# S140039_EMS_3HP_DS.net
KiCad netlist of a schematic drawn in EAGLE
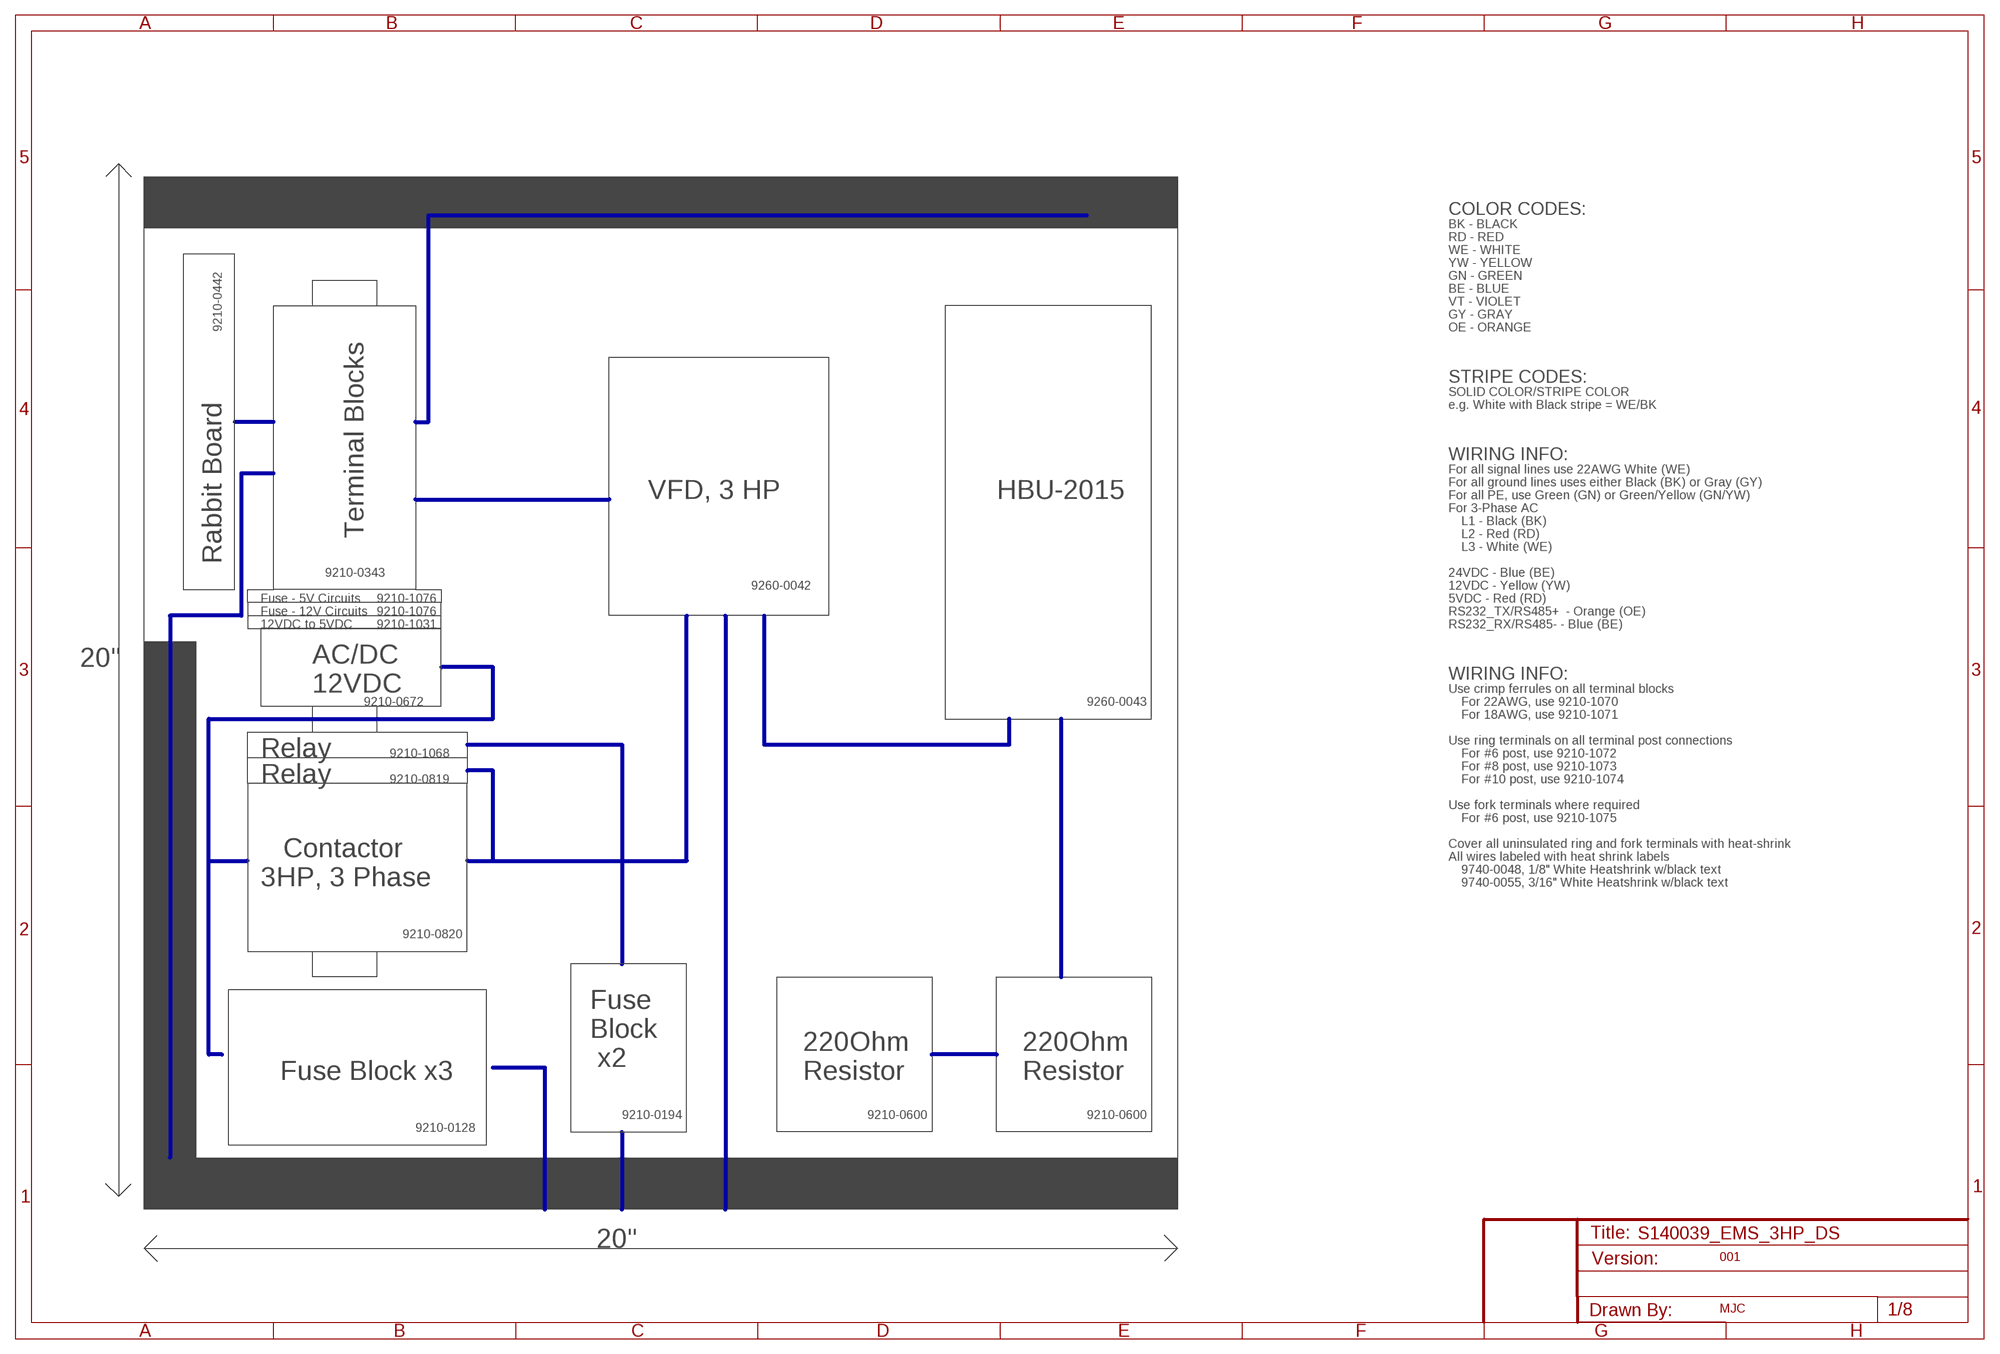
[diagram p0: schematic, sheet 1]
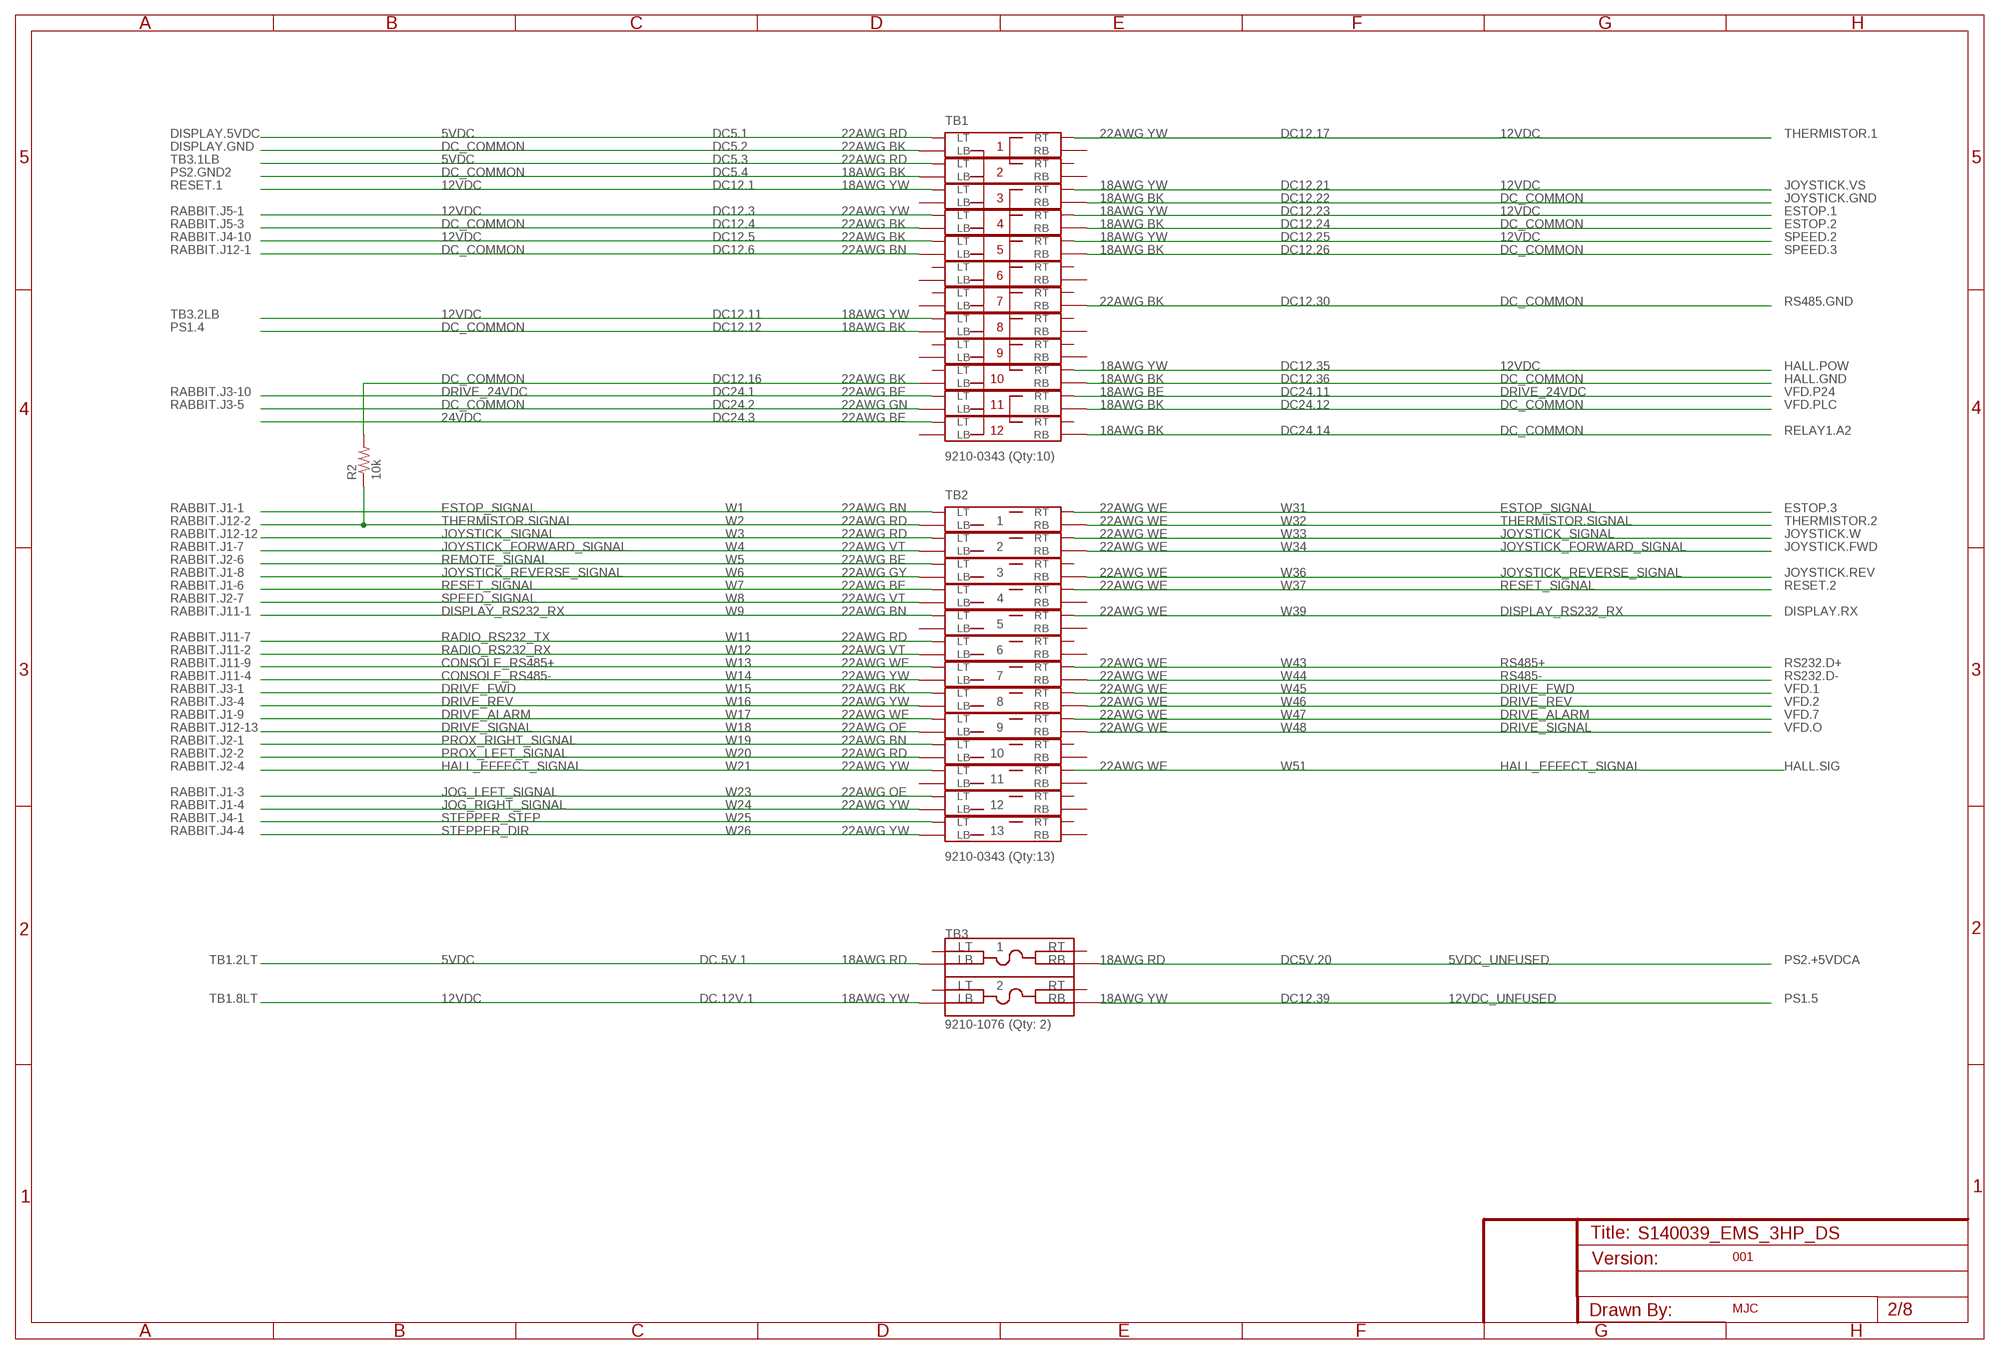
[diagram p1: schematic, sheet 2]
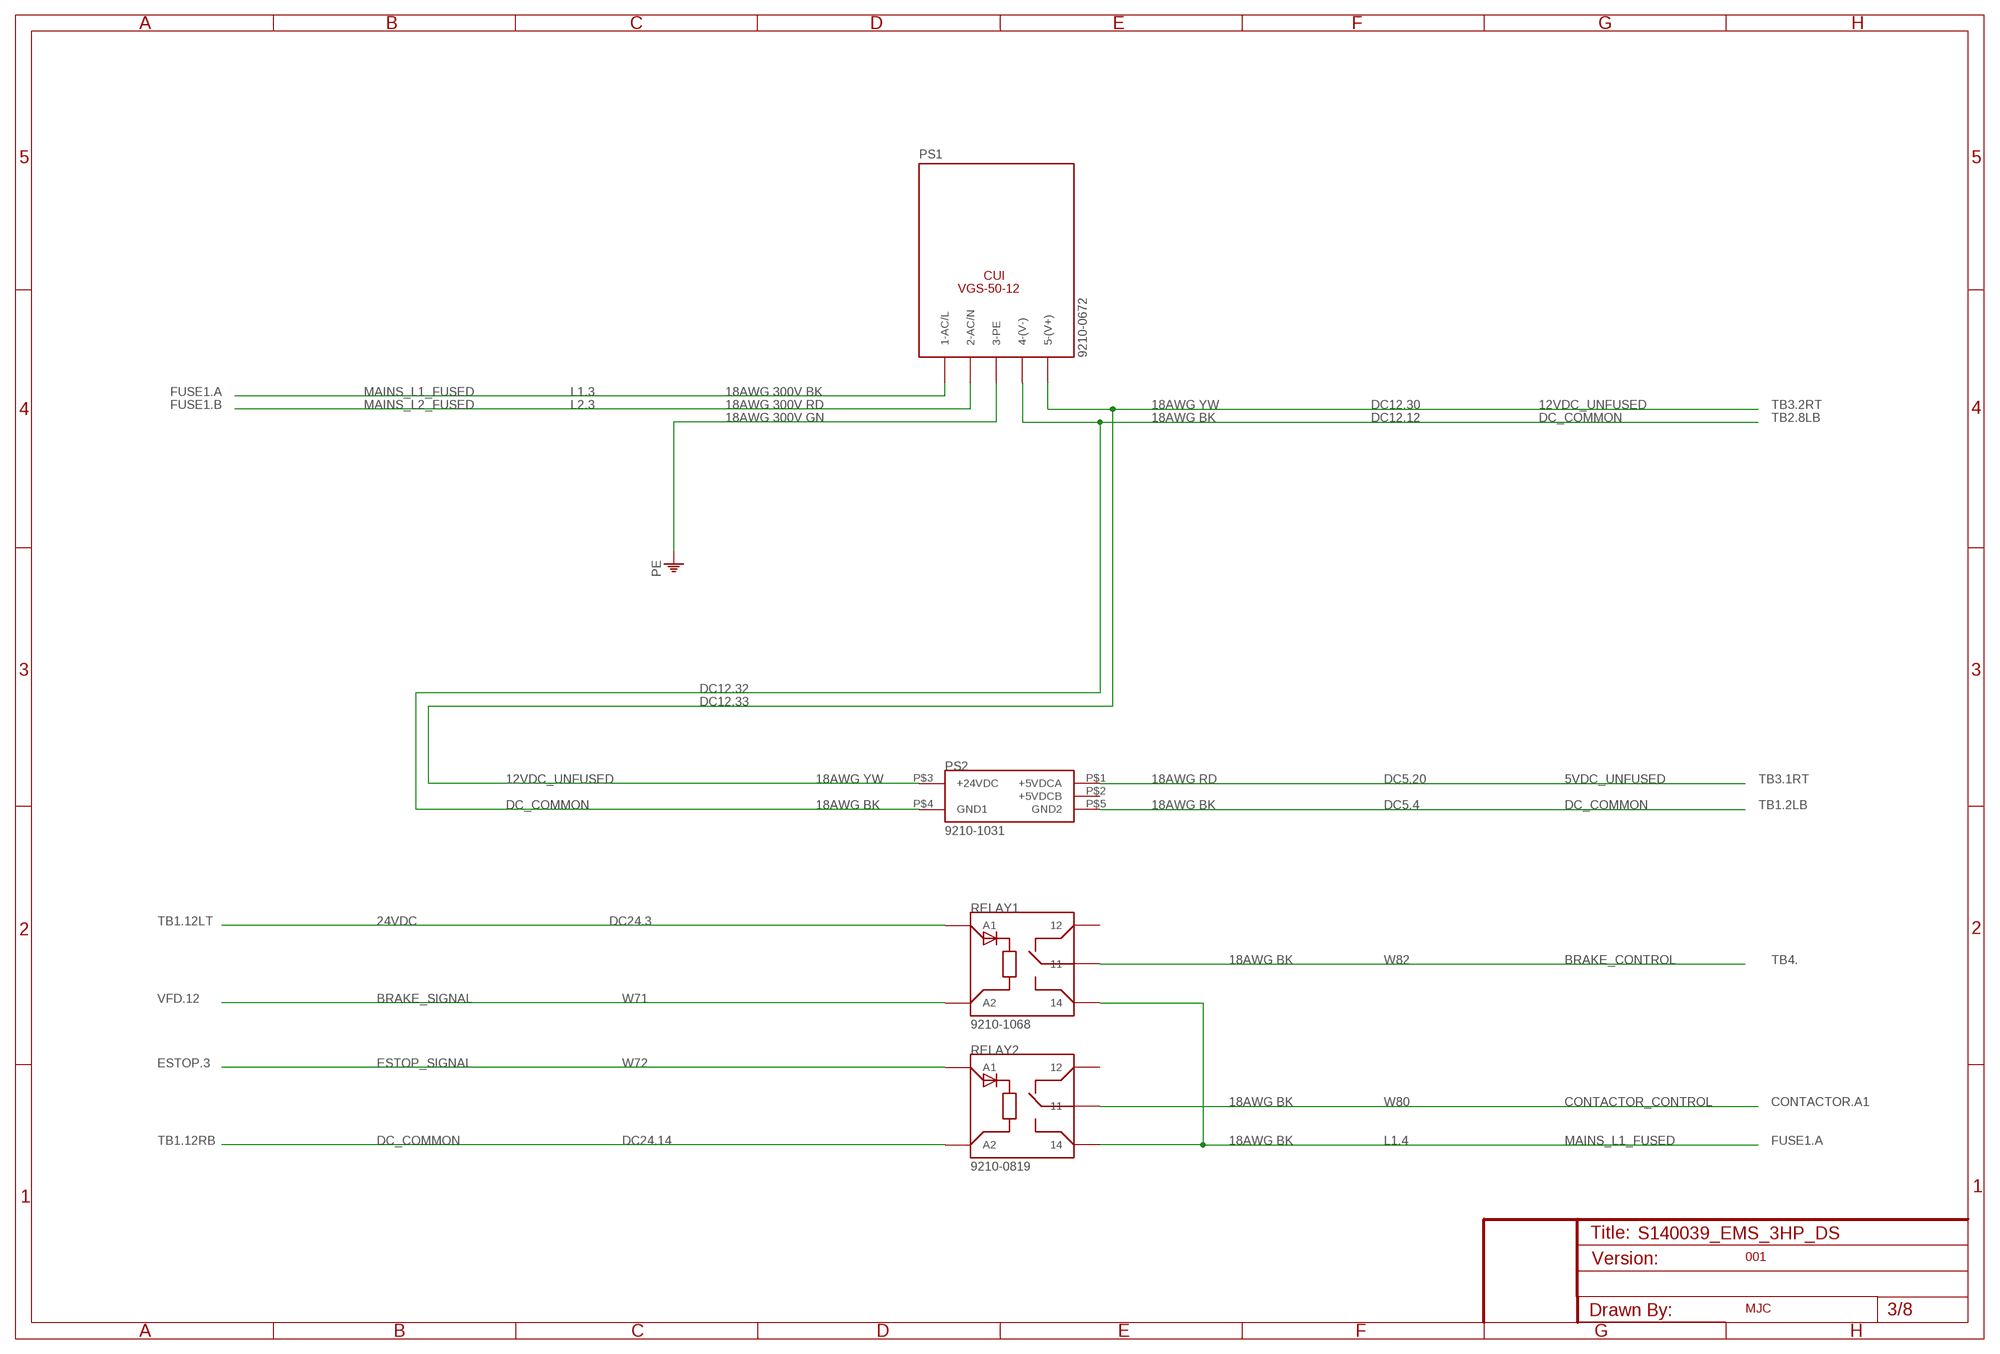
[diagram p2: schematic, sheet 3]
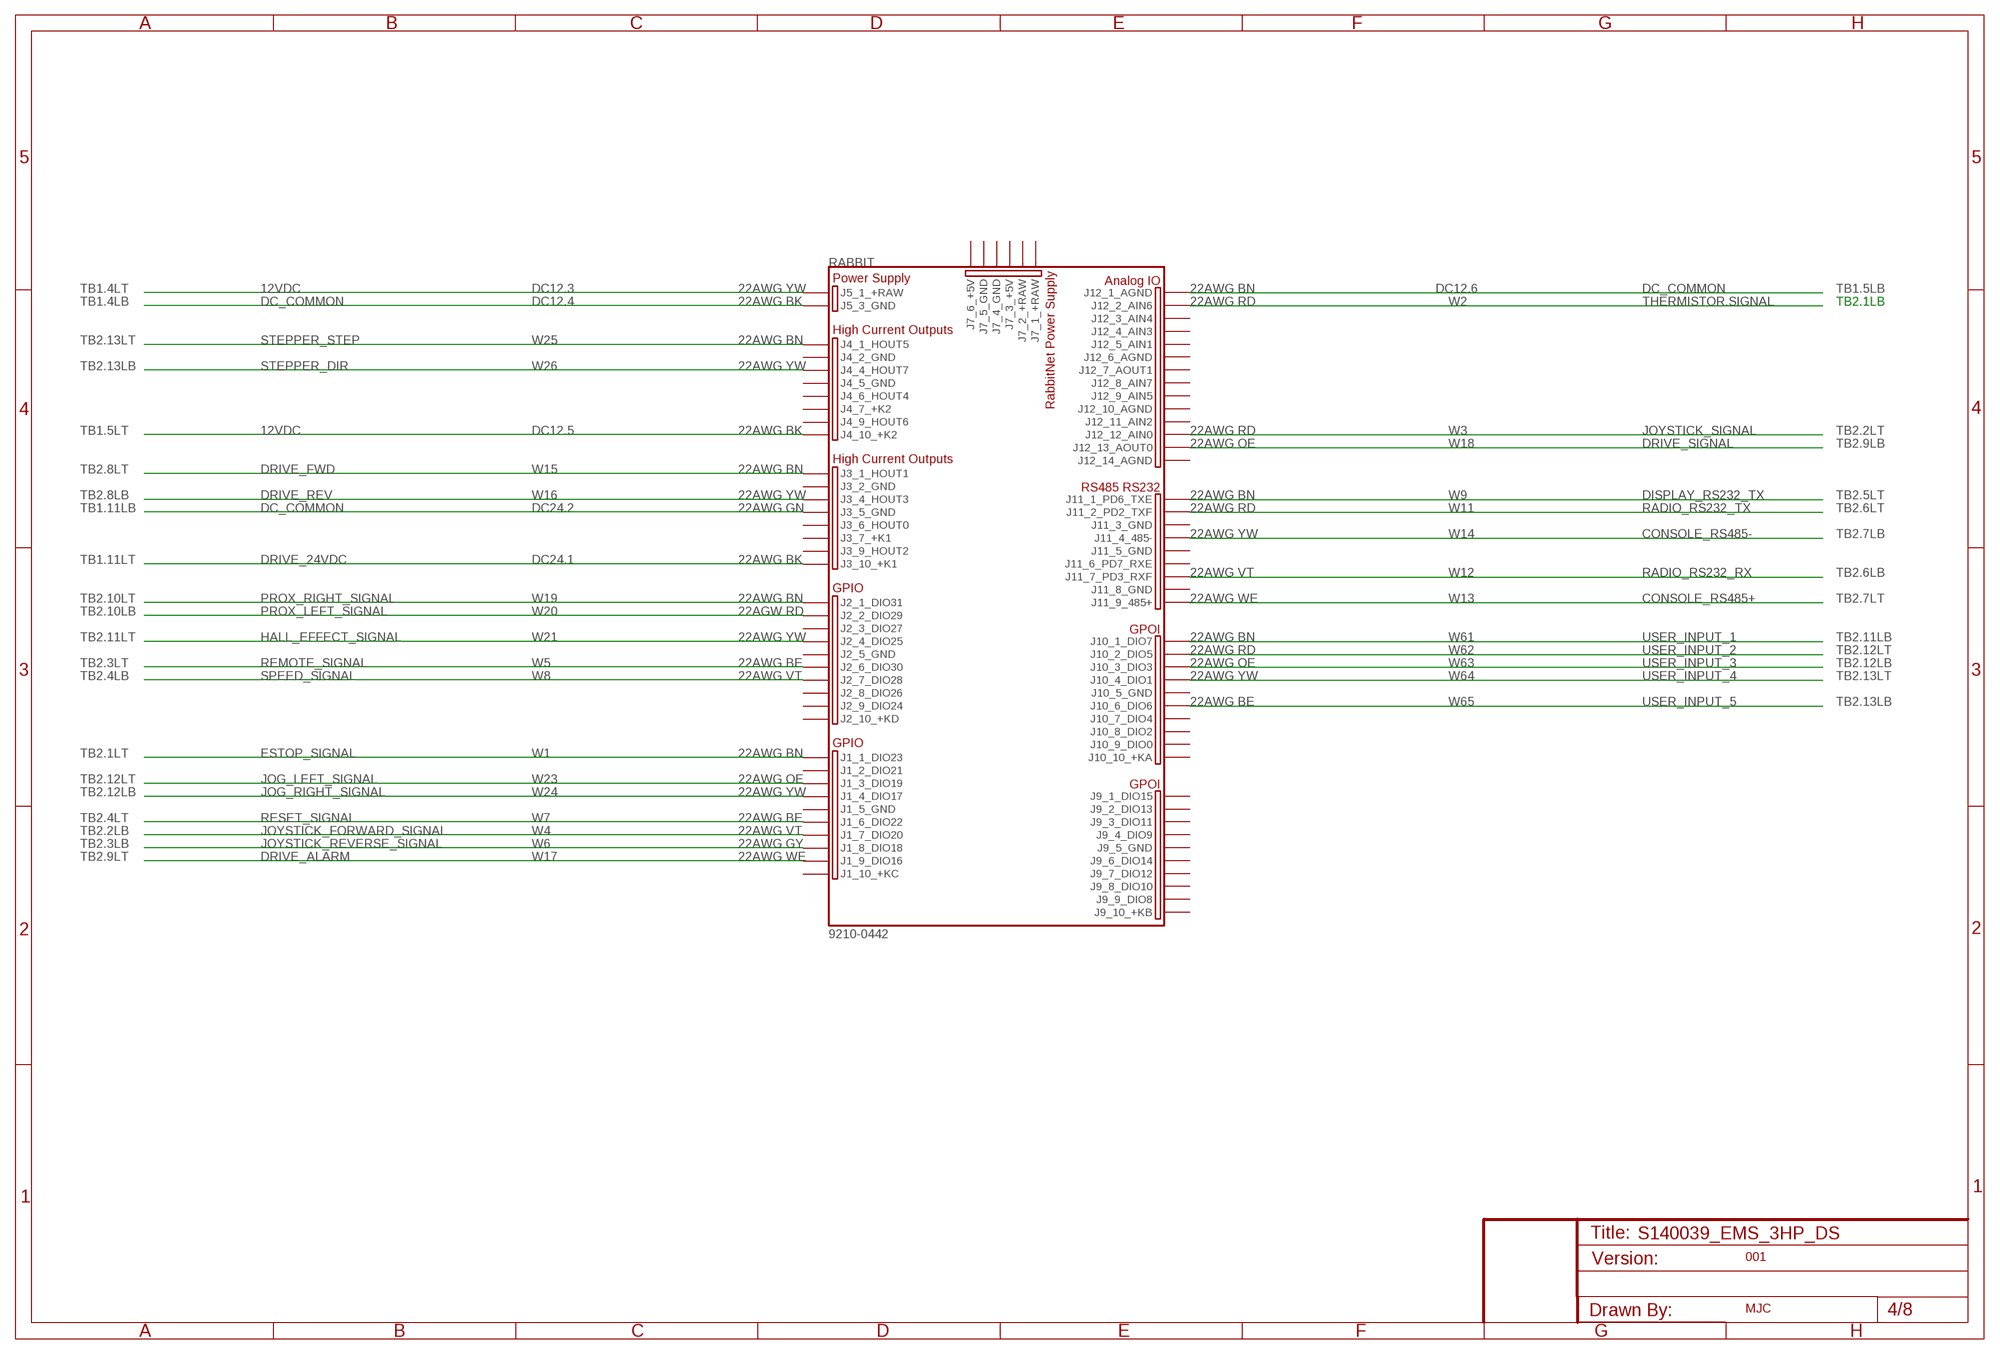
[diagram p3: schematic, sheet 4]
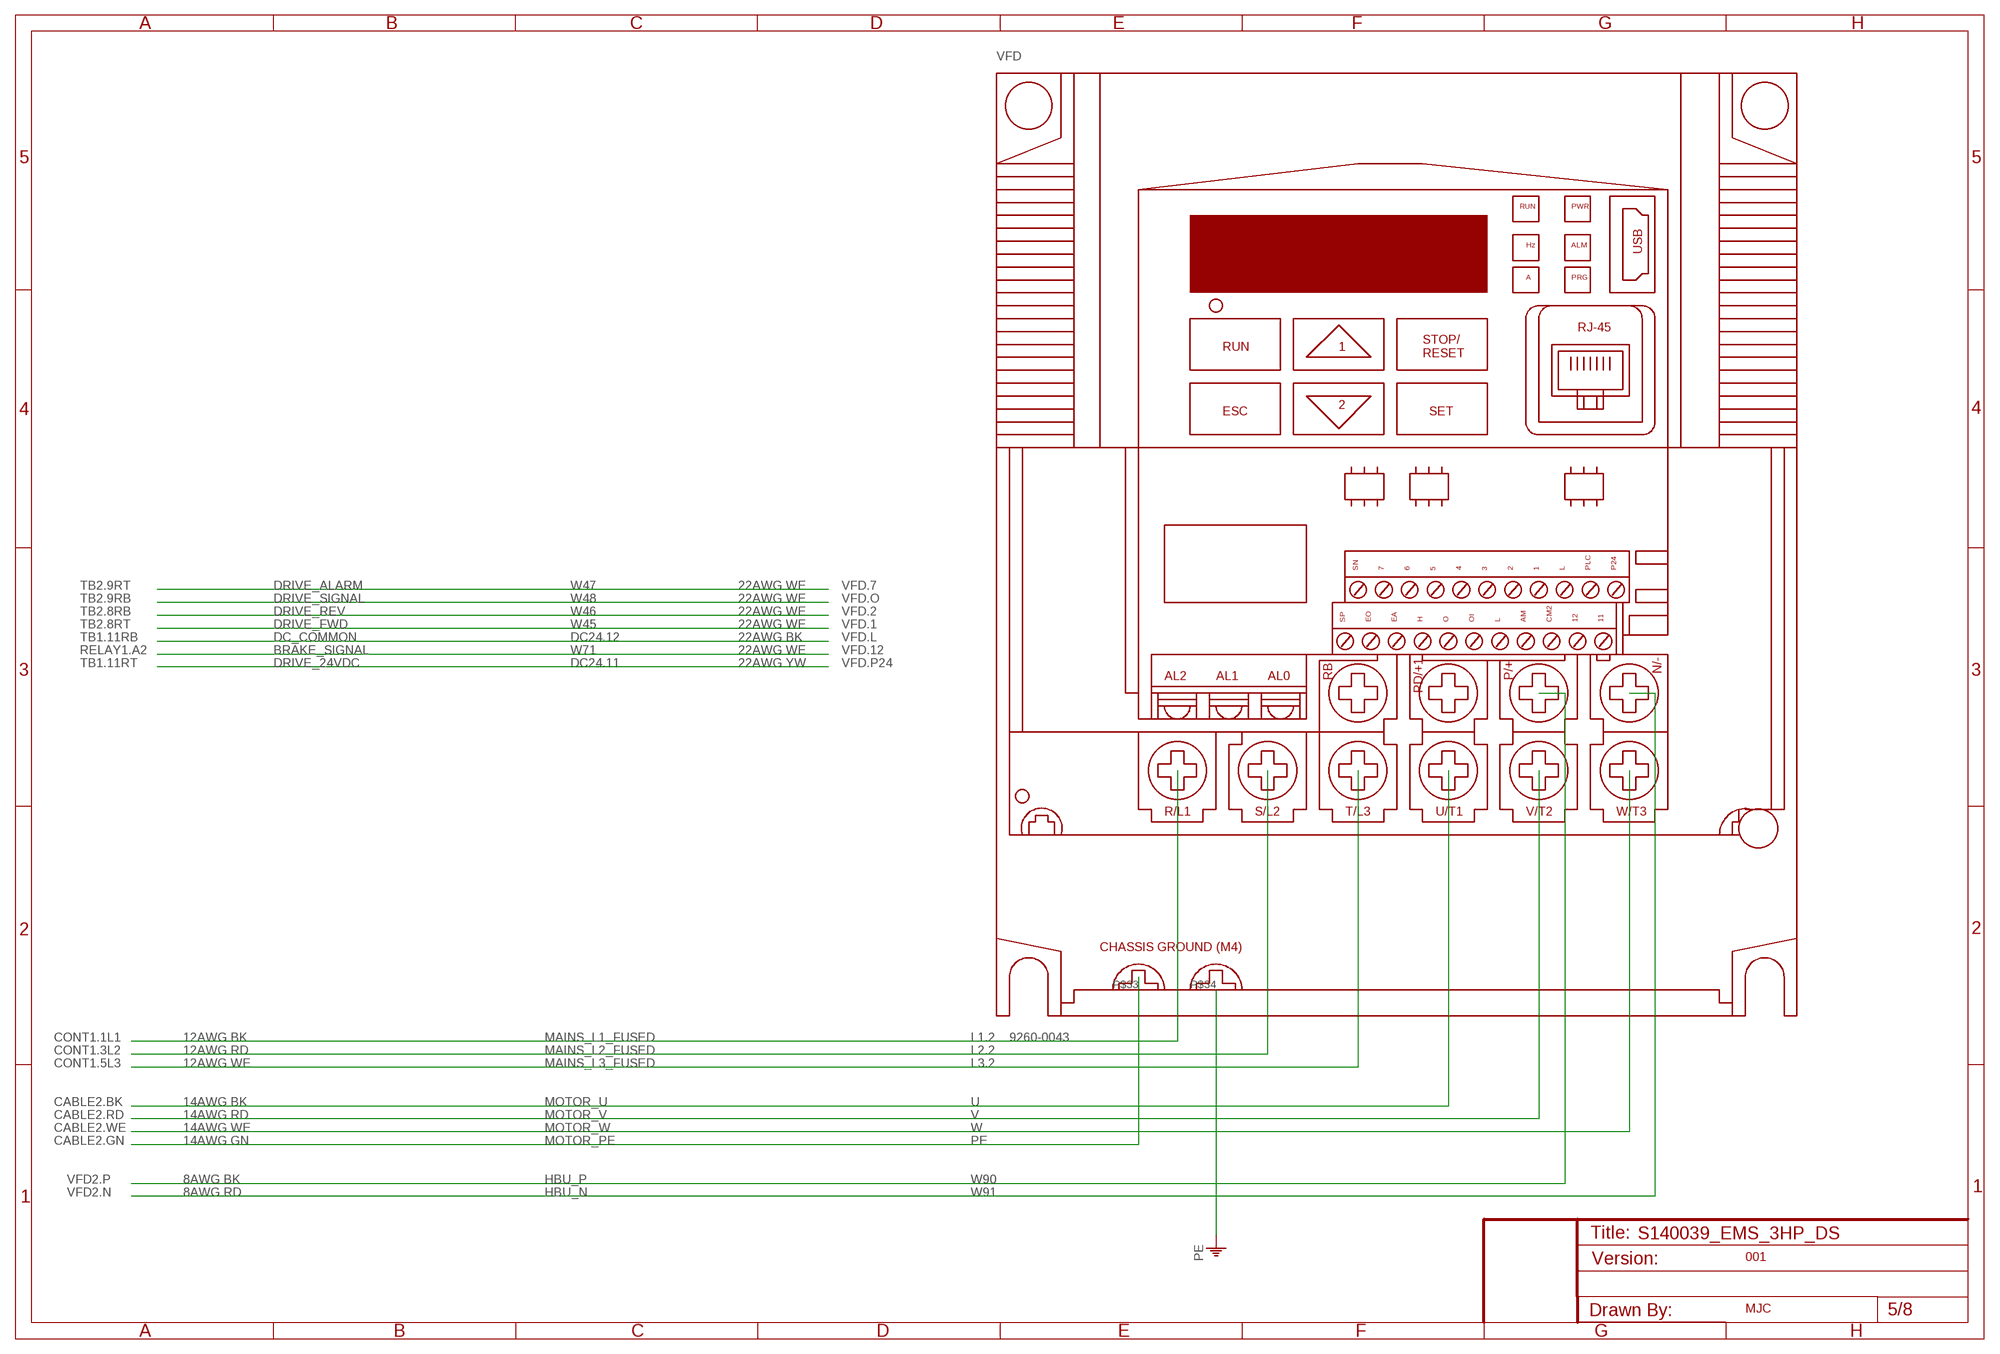
[diagram p4: schematic, sheet 5]
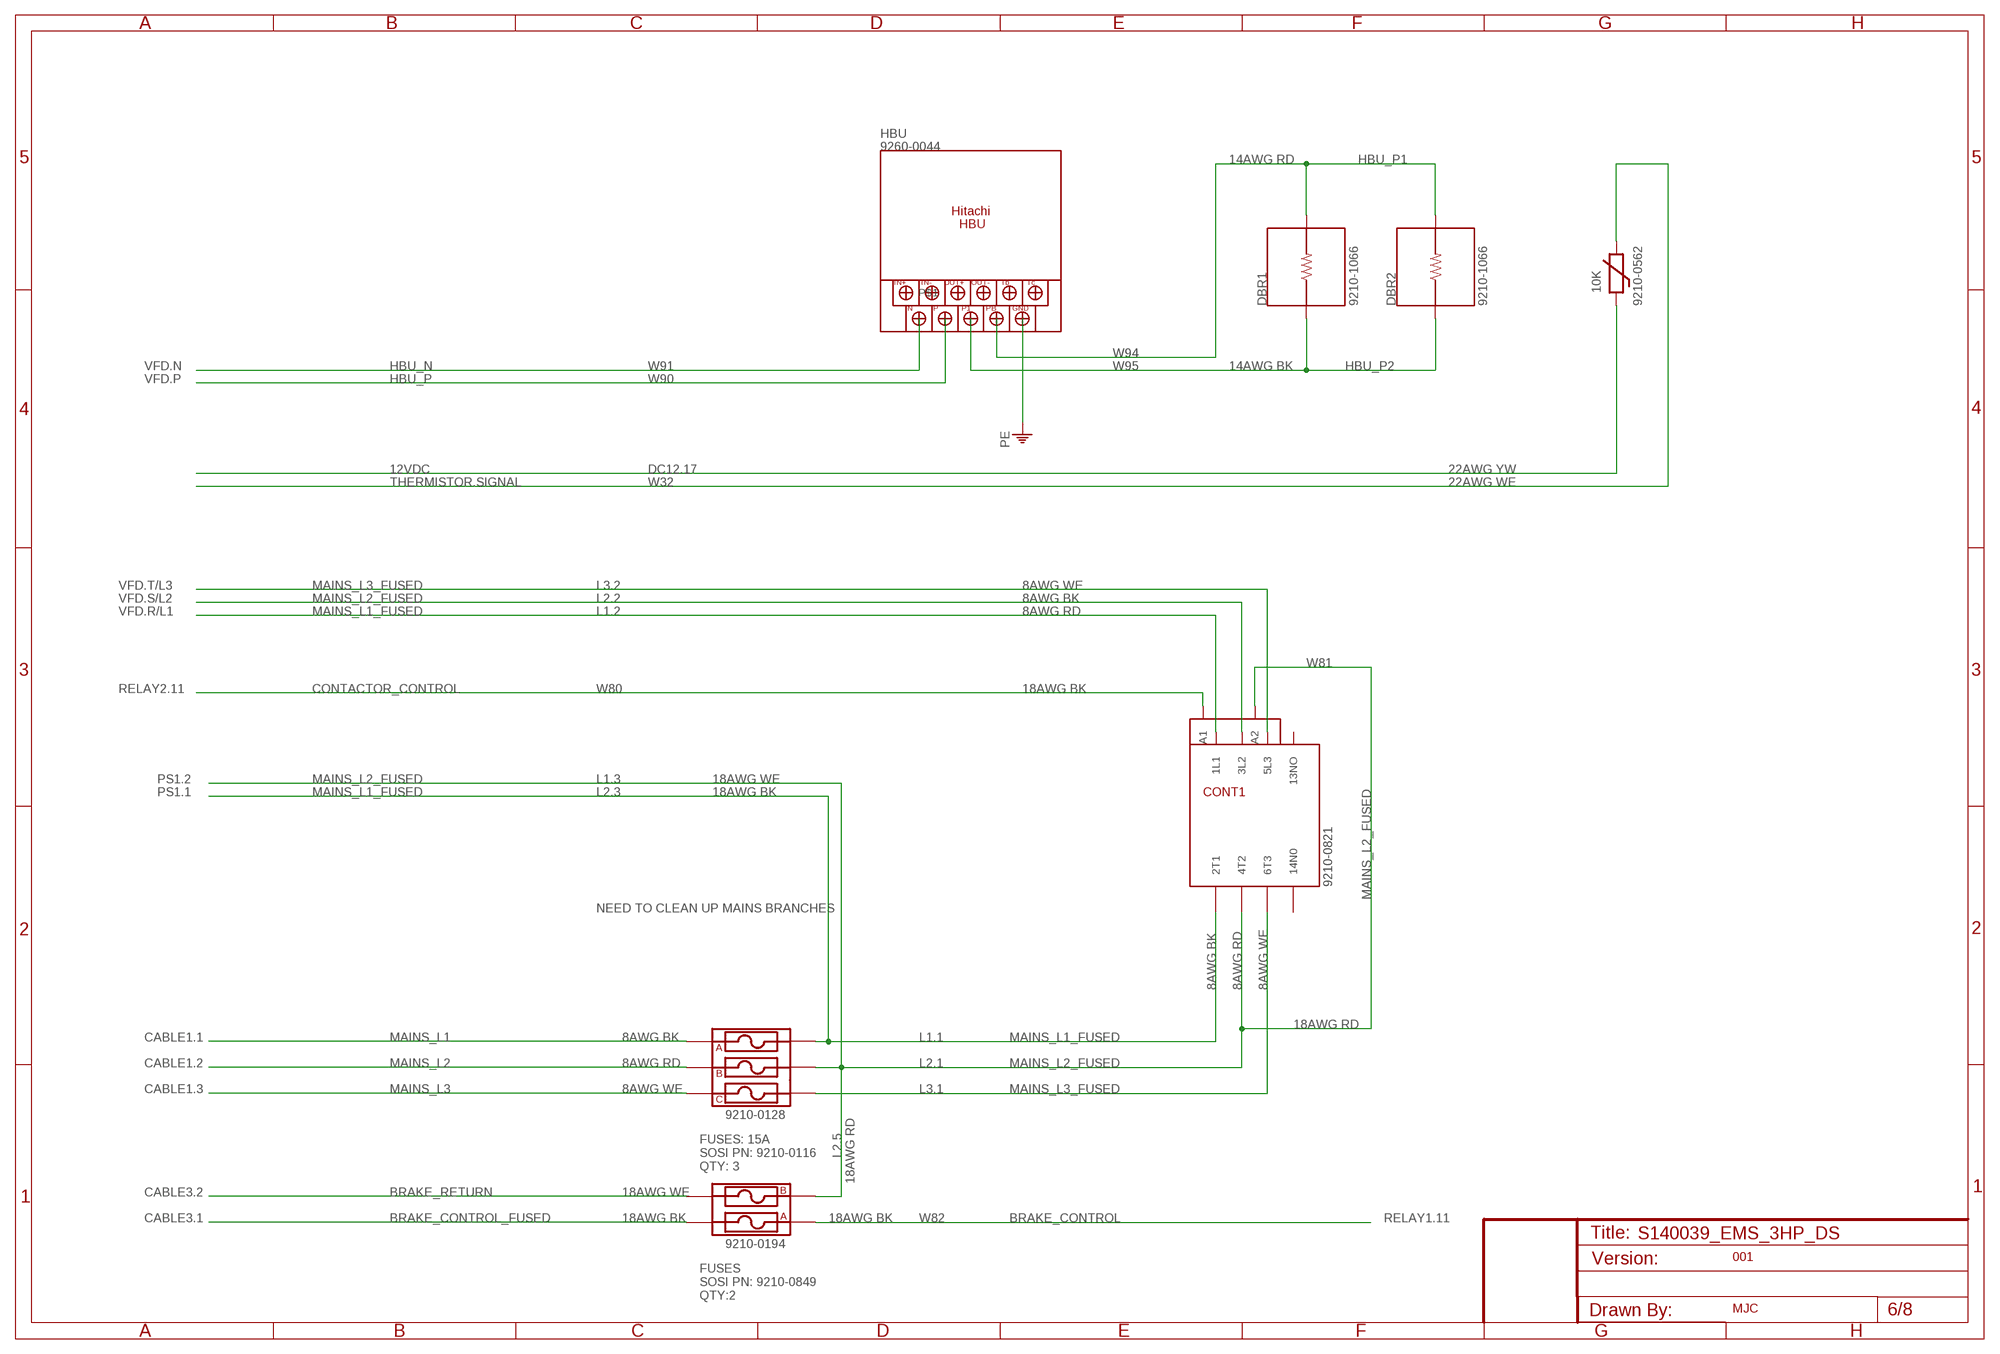
[diagram p5: schematic, sheet 6]
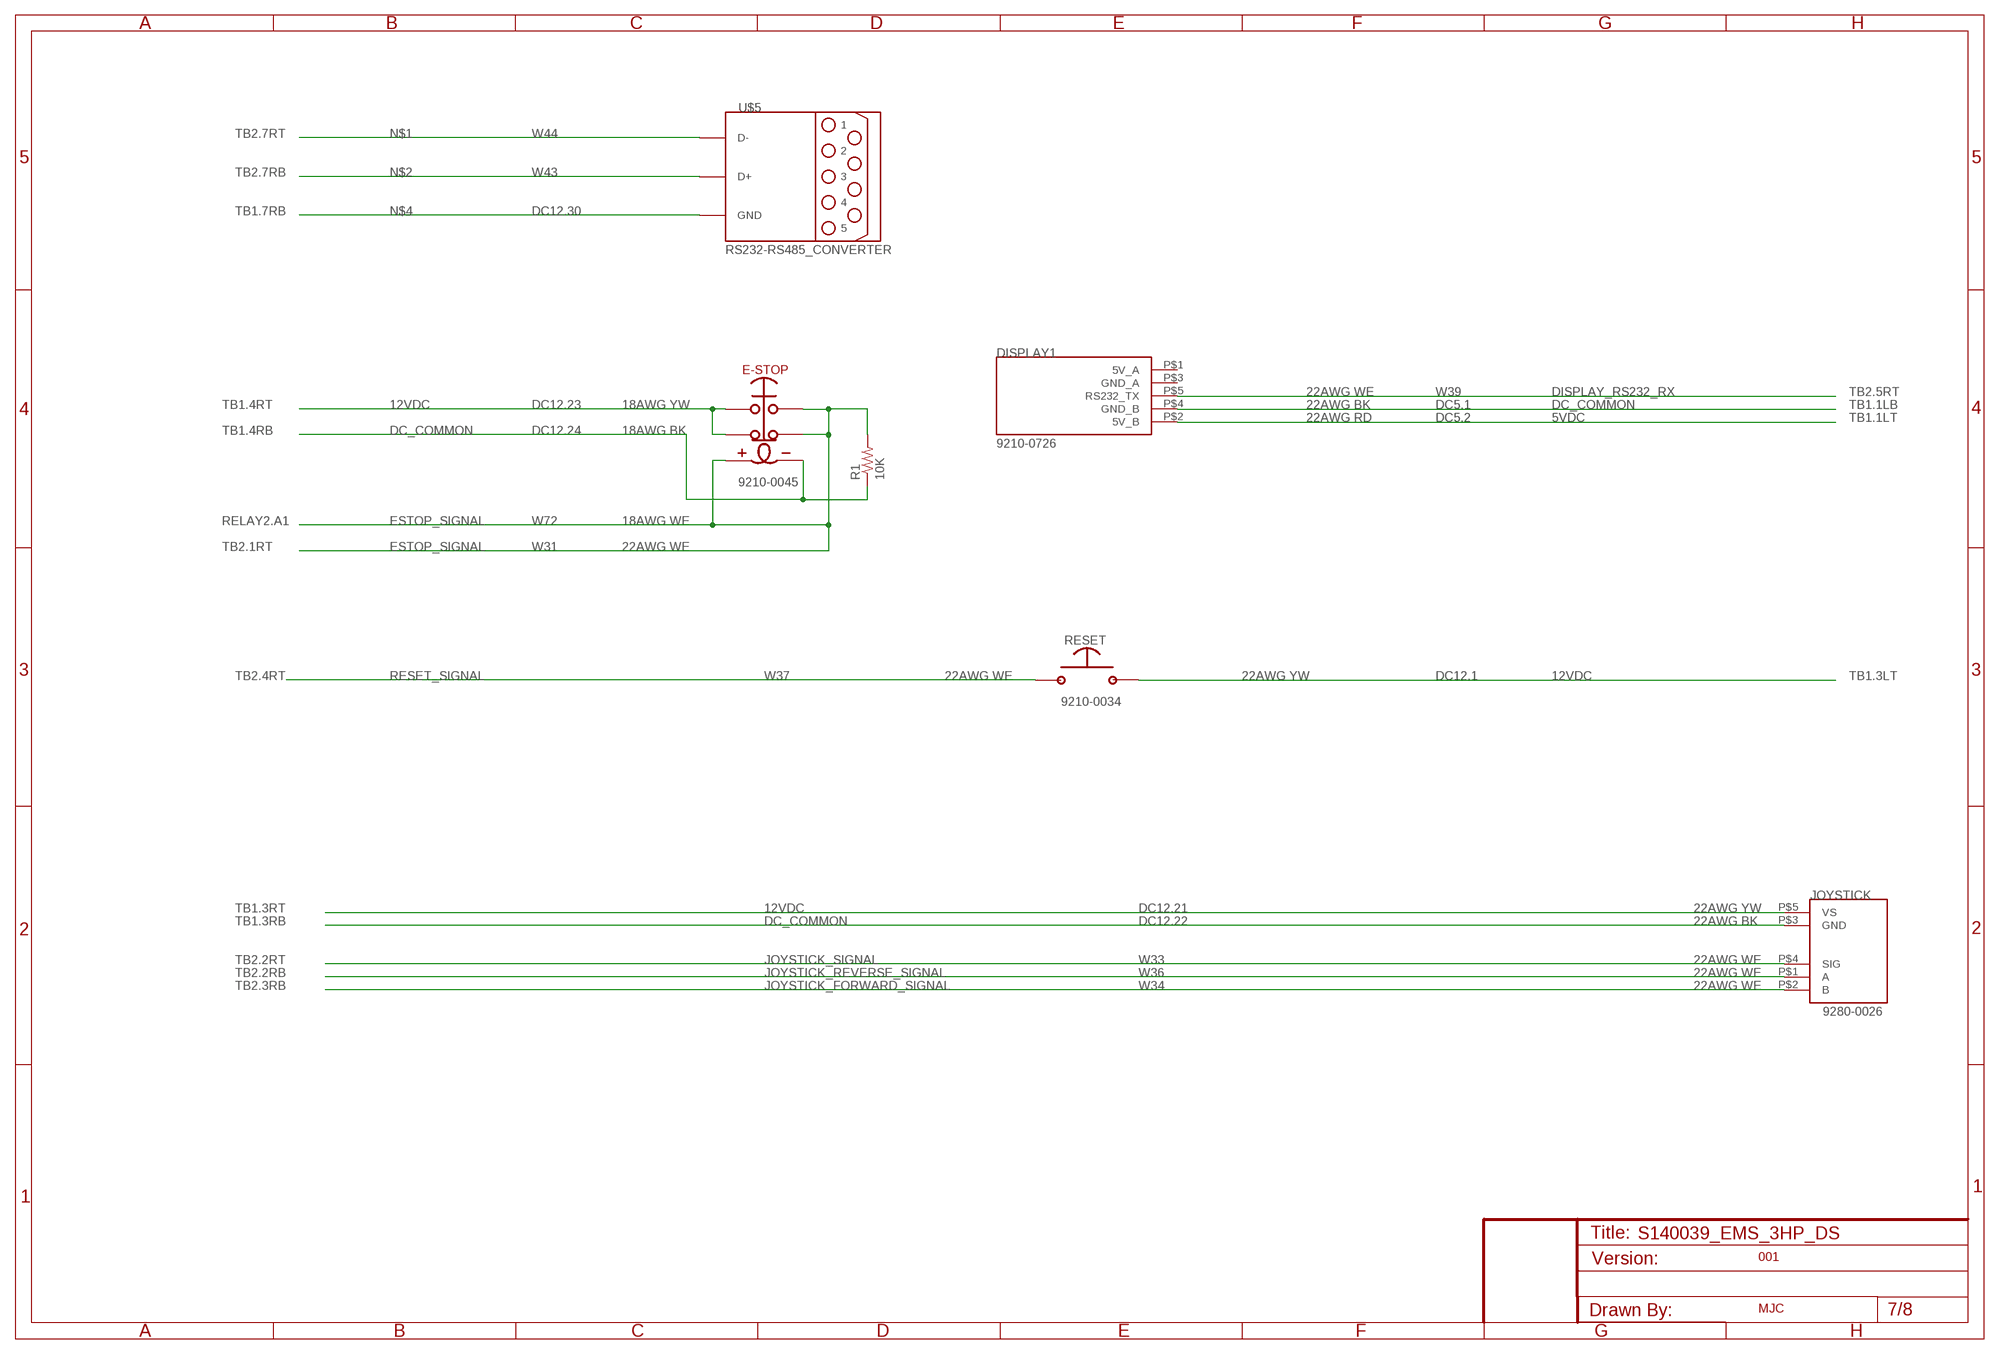
[diagram p6: schematic, sheet 7]
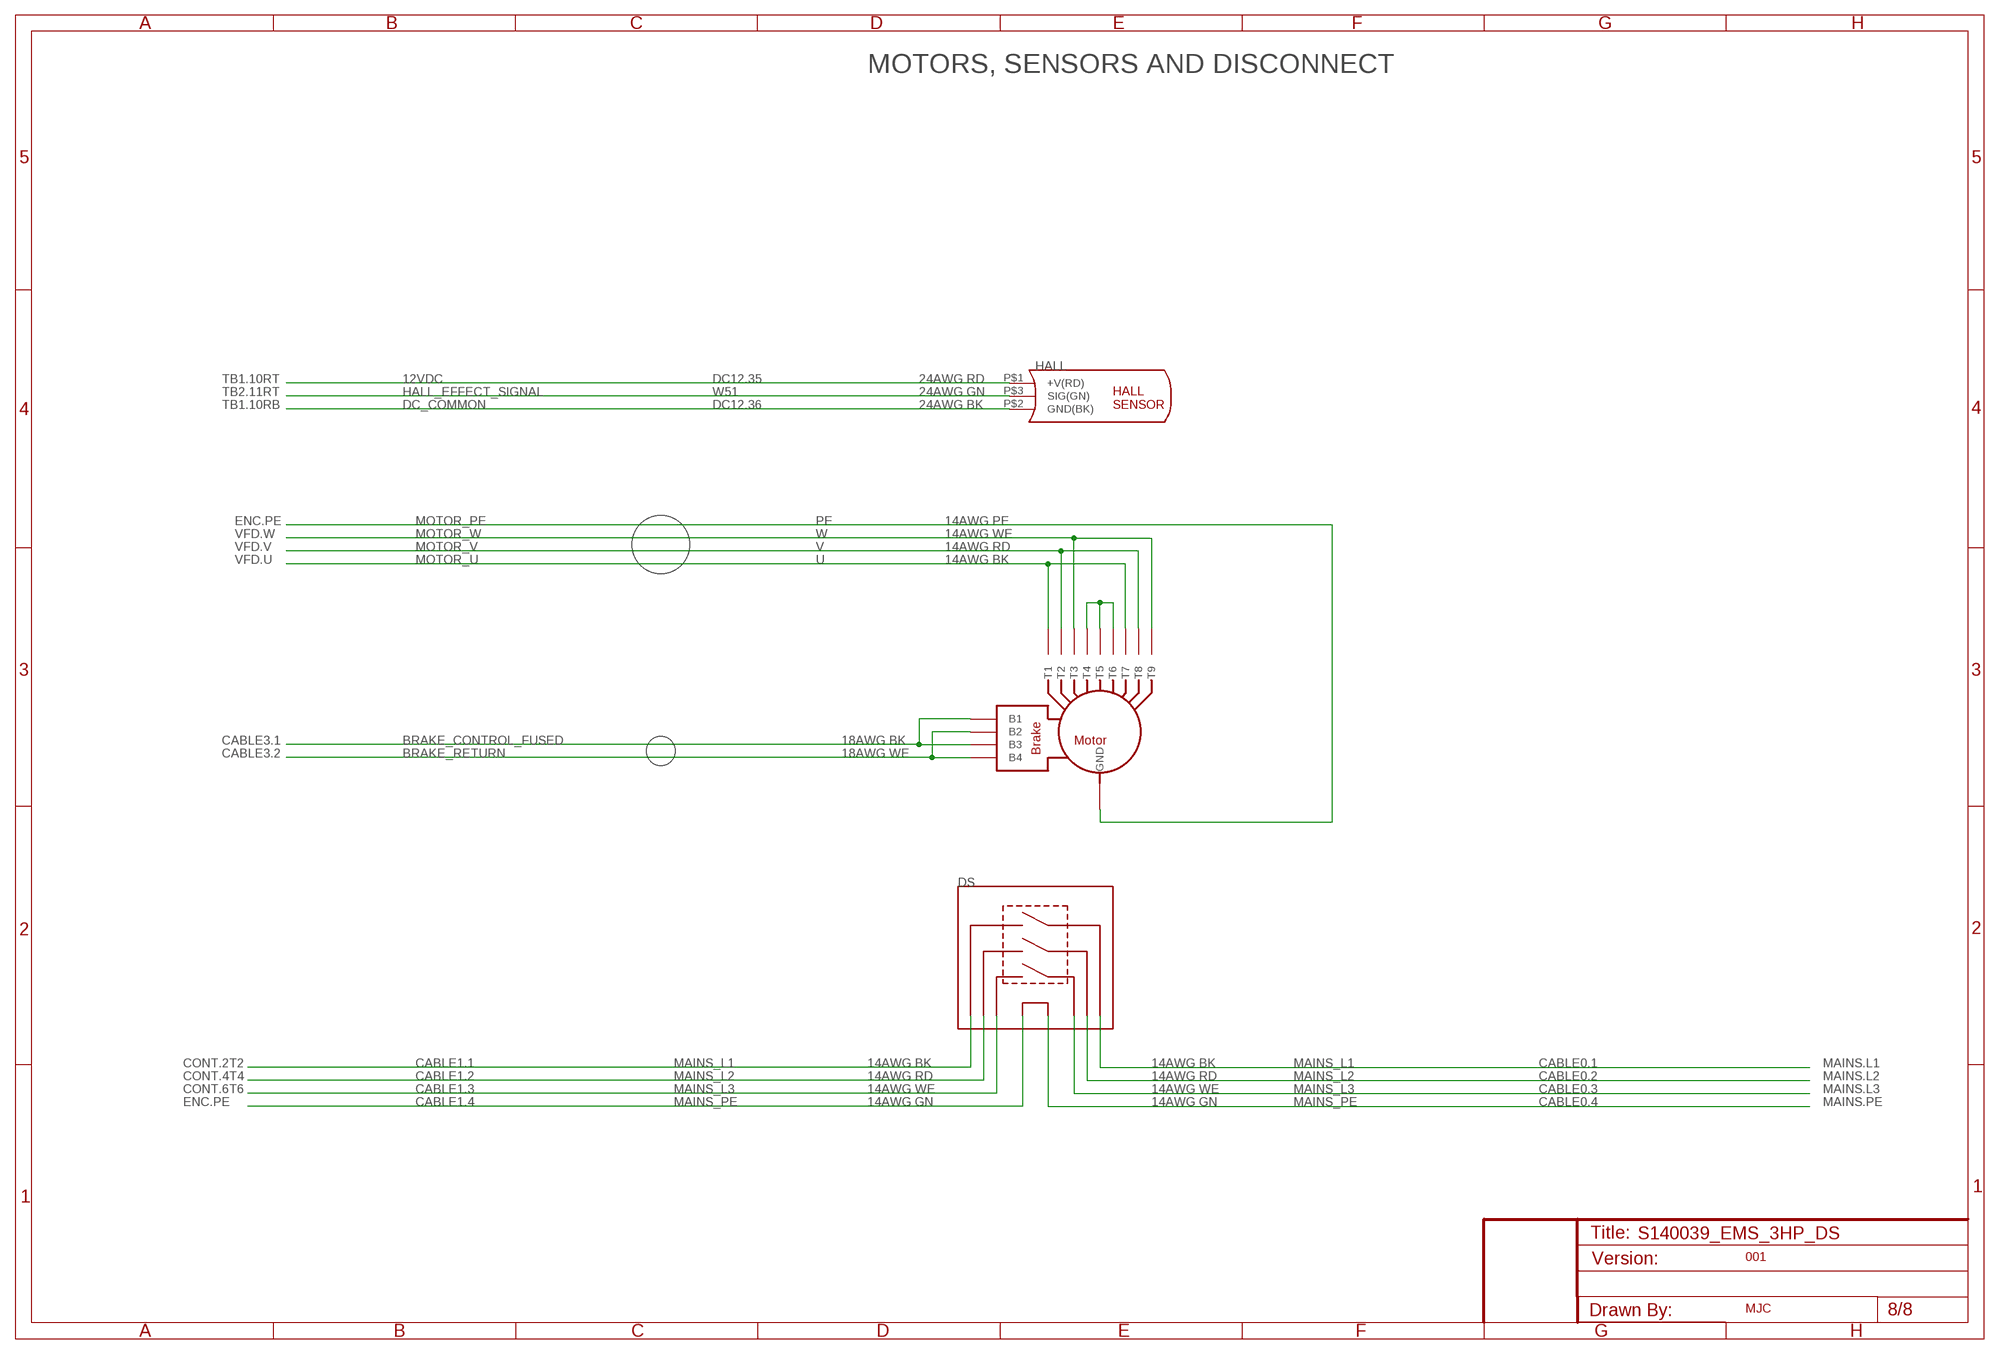
[diagram p7: schematic, sheet 8]

(export (version "E")
  (design (tool "Eeschema 10.0.6"))
  (components
    (comp (ref "CPU1")
      (value "RABBIT_BL4S200(RCM4310)")
      (footprint "eagle-import:RABBIT_BL4S200")
      (libsource (lib "eagle-import") (part "RABBIT_BL4S200(RCM4310)"))
    )
    (comp (ref "DS")
      (value "DISCONNECT_SWITCH")
      (footprint "eagle-import:BOGUS")
      (libsource (lib "eagle-import") (part "DISCONNECT_SWITCH"))
    )
    (comp (ref "HALL")
      (value "DRUM_SENSOR")
      (footprint "eagle-import:BOGUS")
      (libsource (lib "eagle-import") (part "DRUM_SENSOR"))
    )
    (comp (ref "U$11")
      (value "MOTOR_3PH")
      (footprint "eagle-import:BOGUS")
      (libsource (lib "eagle-import") (part "MOTOR_3PH"))
    )
    (comp (ref "CONT1")
      (value "CONTACTOR_3PHASE")
      (footprint "eagle-import:BOGUS")
      (libsource (lib "eagle-import") (part "CONTACTOR_3PHASE"))
    )
    (comp (ref "DBR1")
      (value "100 Ohm")
      (footprint "eagle-import:0204_5")
      (libsource (lib "eagle-import") (part "R-DYNAMIC_BRAKE"))
    )
    (comp (ref "DBR2")
      (value "100 Ohm")
      (footprint "eagle-import:0204_5")
      (libsource (lib "eagle-import") (part "R-DYNAMIC_BRAKE"))
    )
    (comp (ref "FUSE1")
      (value "FUSE_HOLDER_3-POLE")
      (footprint "eagle-import:BOGUS")
      (libsource (lib "eagle-import") (part "FUSE_HOLDER_3-POLE"))
    )
    (comp (ref "HBU")
      (value "HITACHI_HBU-2030")
      (footprint "eagle-import:BOGUS")
      (libsource (lib "eagle-import") (part "HITACHI_HBU-2030"))
    )
    (comp (ref "U$6")
      (value "FUSE_HOLDER_2-POLE")
      (footprint "eagle-import:BOGUS")
      (libsource (lib "eagle-import") (part "FUSE_HOLDER_2-POLE"))
    )
    (comp (ref "U$14")
      (value "10K")
      (footprint "eagle-import:BOGUS")
      (libsource (lib "eagle-import") (part "THERMISTOR"))
    )
    (comp (ref "R2")
      (value "10k")
      (footprint "eagle-import:0204_5")
      (libsource (lib "eagle-import") (part "R-US_0204/5"))
    )
    (comp (ref "U$1")
      (value "TB_3031160_1POS")
      (footprint "eagle-import:BOGUS")
      (libsource (lib "eagle-import") (part "TB_3031160_1POS"))
    )
    (comp (ref "U$2")
      (value "TB_3031160_1POS")
      (footprint "eagle-import:BOGUS")
      (libsource (lib "eagle-import") (part "TB_3031160_1POS"))
    )
    (comp (ref "U$4")
      (value "TB_3031160_1POS")
      (footprint "eagle-import:BOGUS")
      (libsource (lib "eagle-import") (part "TB_3031160_1POS"))
    )
    (comp (ref "U$7")
      (value "TB_3031160_1POS")
      (footprint "eagle-import:BOGUS")
      (libsource (lib "eagle-import") (part "TB_3031160_1POS"))
    )
    (comp (ref "U$8")
      (value "TB_3031160_1POS")
      (footprint "eagle-import:BOGUS")
      (libsource (lib "eagle-import") (part "TB_3031160_1POS"))
    )
    (comp (ref "U$9")
      (value "TB_FUSE_DDFL4ULR")
      (footprint "eagle-import:BOGUS")
      (libsource (lib "eagle-import") (part "TB_FUSE_DDFL4ULR"))
    )
    (comp (ref "U$10")
      (value "TB_FUSE_DDFL4ULR")
      (footprint "eagle-import:BOGUS")
      (libsource (lib "eagle-import") (part "TB_FUSE_DDFL4ULR"))
    )
    (comp (ref "U$16")
      (value "TB_3031160_1POS")
      (footprint "eagle-import:BOGUS")
      (libsource (lib "eagle-import") (part "TB_3031160_1POS"))
    )
    (comp (ref "U$17")
      (value "TB_3031160_1POS")
      (footprint "eagle-import:BOGUS")
      (libsource (lib "eagle-import") (part "TB_3031160_1POS"))
    )
    (comp (ref "U$18")
      (value "TB_3031160_1POS")
      (footprint "eagle-import:BOGUS")
      (libsource (lib "eagle-import") (part "TB_3031160_1POS"))
    )
    (comp (ref "U$19")
      (value "TB_3031160_1POS")
      (footprint "eagle-import:BOGUS")
      (libsource (lib "eagle-import") (part "TB_3031160_1POS"))
    )
    (comp (ref "U$20")
      (value "TB_3031160_1POS")
      (footprint "eagle-import:BOGUS")
      (libsource (lib "eagle-import") (part "TB_3031160_1POS"))
    )
    (comp (ref "U$21")
      (value "TB_3031160_1POS")
      (footprint "eagle-import:BOGUS")
      (libsource (lib "eagle-import") (part "TB_3031160_1POS"))
    )
    (comp (ref "U$22")
      (value "TB_3031160_1POS")
      (footprint "eagle-import:BOGUS")
      (libsource (lib "eagle-import") (part "TB_3031160_1POS"))
    )
    (comp (ref "U$23")
      (value "TB_3031160_1POS")
      (footprint "eagle-import:BOGUS")
      (libsource (lib "eagle-import") (part "TB_3031160_1POS"))
    )
    (comp (ref "U$24")
      (value "TB_3031160_1POS")
      (footprint "eagle-import:BOGUS")
      (libsource (lib "eagle-import") (part "TB_3031160_1POS"))
    )
    (comp (ref "U$25")
      (value "TB_3031160_1POS")
      (footprint "eagle-import:BOGUS")
      (libsource (lib "eagle-import") (part "TB_3031160_1POS"))
    )
    (comp (ref "U$26")
      (value "TB_3031160_1POS")
      (footprint "eagle-import:BOGUS")
      (libsource (lib "eagle-import") (part "TB_3031160_1POS"))
    )
    (comp (ref "U$27")
      (value "TB_3031160_1POS")
      (footprint "eagle-import:BOGUS")
      (libsource (lib "eagle-import") (part "TB_3031160_1POS"))
    )
    (comp (ref "U$28")
      (value "TB_3031160_1POS")
      (footprint "eagle-import:BOGUS")
      (libsource (lib "eagle-import") (part "TB_3031160_1POS"))
    )
    (comp (ref "U$29")
      (value "TB_3031160_1POS")
      (footprint "eagle-import:BOGUS")
      (libsource (lib "eagle-import") (part "TB_3031160_1POS"))
    )
    (comp (ref "U$30")
      (value "TB_3031160_1POS")
      (footprint "eagle-import:BOGUS")
      (libsource (lib "eagle-import") (part "TB_3031160_1POS"))
    )
    (comp (ref "U$31")
      (value "TB_3031160_1POS")
      (footprint "eagle-import:BOGUS")
      (libsource (lib "eagle-import") (part "TB_3031160_1POS"))
    )
    (comp (ref "U$32")
      (value "TB_3031160_1POS")
      (footprint "eagle-import:BOGUS")
      (libsource (lib "eagle-import") (part "TB_3031160_1POS"))
    )
    (comp (ref "U$33")
      (value "TB_3031160_1POS")
      (footprint "eagle-import:BOGUS")
      (libsource (lib "eagle-import") (part "TB_3031160_1POS"))
    )
    (comp (ref "U$34")
      (value "TB_3031160_1POS")
      (footprint "eagle-import:BOGUS")
      (libsource (lib "eagle-import") (part "TB_3031160_1POS"))
    )
    (comp (ref "U$35")
      (value "TB_3031160_1POS")
      (footprint "eagle-import:BOGUS")
      (libsource (lib "eagle-import") (part "TB_3031160_1POS"))
    )
    (comp (ref "PS1")
      (value "DC-DC_CONVERTER_VGS-50-12")
      (footprint "eagle-import:BOGUS")
      (libsource (lib "eagle-import") (part "DC-DC_CONVERTER_VGS-50-12"))
    )
    (comp (ref "PS2")
      (value "DC-DC_CONVERTER_24V-5V")
      (footprint "eagle-import:BOGUS")
      (libsource (lib "eagle-import") (part "DC-DC_CONVERTER_24V-5V"))
    )
    (comp (ref "RELAY1")
      (value "RELAY_TB")
      (footprint "eagle-import:BOGUS")
      (libsource (lib "eagle-import") (part "RELAY_TB"))
    )
    (comp (ref "RELAY2")
      (value "RELAY_TB")
      (footprint "eagle-import:BOGUS")
      (libsource (lib "eagle-import") (part "RELAY_TB"))
    )
    (comp (ref "DISPLAY1")
      (value "SEETRON_GLO-416")
      (footprint "eagle-import:BOGUS")
      (libsource (lib "eagle-import") (part "SEETRON_GLO-416"))
    )
    (comp (ref "JOYSTICK")
      (value "JOYSTICK")
      (footprint "eagle-import:BOGUS")
      (libsource (lib "eagle-import") (part "JOYSTICK"))
    )
    (comp (ref "R1")
      (value "10K")
      (footprint "eagle-import:AXIAL-0.3")
      (libsource (lib "eagle-import") (part "RESISTORAXIAL-0.3"))
    )
    (comp (ref "RESET")
      (value "SWITCH_MOM_NO")
      (footprint "eagle-import:BOGUS")
      (libsource (lib "eagle-import") (part "SWITCH_MOM_NO"))
    )
    (comp (ref "U$3")
      (value "SWITCH_ESTOP_LIGHTED")
      (footprint "eagle-import:BOGUS")
      (libsource (lib "eagle-import") (part "SWITCH_ESTOP_LIGHTED"))
    )
    (comp (ref "U$5")
      (value "RS232-RS485_CONVERTER")
      (footprint "eagle-import:BOGUS")
      (libsource (lib "eagle-import") (part "RS232-RS485_CONVERTER"))
    )
    (comp (ref "VFD")
      (value "HITACHI_WJ200-022LF")
      (footprint "eagle-import:BOGUS")
      (libsource (lib "eagle-import") (part "HITACHI_WJ200-022LF"))
    )
  )
  (nets
    (net (code "1") (name "5VDC") (class "Default")
      (node (ref "DISPLAY1") (pin "P$2") (pinfunction "5V_B_P$2") (pintype "bidirectional"))
      (node (ref "U$34") (pin "P$2") (pinfunction "LT_P$2") (pintype "bidirectional"))
      (node (ref "U$35") (pin "P$2") (pinfunction "LT_P$2") (pintype "bidirectional"))
      (node (ref "U$9") (pin "P$2") (pinfunction "P$2_P$2") (pintype "bidirectional"))
    )
    (net (code "2") (name "5VDC_UNFUSED") (class "Default")
      (node (ref "PS2") (pin "P$1") (pinfunction "+5VDCA_P$1") (pintype "bidirectional"))
      (node (ref "U$9") (pin "P$4") (pinfunction "P$4_P$4") (pintype "bidirectional"))
    )
    (net (code "3") (name "12VDC") (class "Default")
      (node (ref "CPU1") (pin "P$J4-10") (pinfunction "J4_10_+K2_P$J4-10") (pintype "bidirectional"))
      (node (ref "CPU1") (pin "P$J5-1") (pinfunction "J5_1_+RAW_P$J5-1") (pintype "bidirectional"))
      (node (ref "HALL") (pin "P$1") (pinfunction "+V(RD)_P$1") (pintype "bidirectional"))
      (node (ref "JOYSTICK") (pin "P$5") (pinfunction "VS_P$5") (pintype "bidirectional"))
      (node (ref "RESET") (pin "P$2") (pinfunction "P$2_P$2") (pintype "bidirectional"))
      (node (ref "U$10") (pin "P$2") (pinfunction "P$2_P$2") (pintype "bidirectional"))
      (node (ref "U$14") (pin "P$2") (pinfunction "P$2_P$2") (pintype "bidirectional"))
      (node (ref "U$28") (pin "P$2") (pinfunction "LT_P$2") (pintype "bidirectional"))
      (node (ref "U$3") (pin "P$1") (pinfunction "P$1_P$1") (pintype "bidirectional"))
      (node (ref "U$3") (pin "P$2") (pinfunction "P$2_P$2") (pintype "bidirectional"))
      (node (ref "U$31") (pin "P$2") (pinfunction "LT_P$2") (pintype "bidirectional"))
      (node (ref "U$31") (pin "P$4") (pinfunction "RT_P$4") (pintype "bidirectional"))
      (node (ref "U$32") (pin "P$2") (pinfunction "LT_P$2") (pintype "bidirectional"))
      (node (ref "U$32") (pin "P$4") (pinfunction "RT_P$4") (pintype "bidirectional"))
      (node (ref "U$33") (pin "P$2") (pinfunction "LT_P$2") (pintype "bidirectional"))
      (node (ref "U$33") (pin "P$4") (pinfunction "RT_P$4") (pintype "bidirectional"))
      (node (ref "U$35") (pin "P$4") (pinfunction "RT_P$4") (pintype "bidirectional"))
      (node (ref "U$8") (pin "P$4") (pinfunction "RT_P$4") (pintype "bidirectional"))
    )
    (net (code "4") (name "12VDC_UNFUSED") (class "Default")
      (node (ref "PS1") (pin "P$5") (pinfunction "5-(V+)_P$5") (pintype "bidirectional"))
      (node (ref "PS2") (pin "P$3") (pinfunction "+24VDC_P$3") (pintype "bidirectional"))
      (node (ref "U$10") (pin "P$4") (pinfunction "P$4_P$4") (pintype "bidirectional"))
    )
    (net (code "5") (name "24VDC") (class "Default")
      (node (ref "RELAY1") (pin "P$4") (pinfunction "A1_P$4") (pintype "bidirectional"))
      (node (ref "U$26") (pin "P$2") (pinfunction "LT_P$2") (pintype "bidirectional"))
    )
    (net (code "6") (name "BRAKE_CONTROL") (class "Default")
      (node (ref "RELAY1") (pin "P$1") (pinfunction "11_P$1") (pintype "bidirectional"))
      (node (ref "U$6") (pin "P$2") (pinfunction "P$2_P$2") (pintype "bidirectional"))
    )
    (net (code "7") (name "BRAKE_CONTROL_FUSED") (class "Default")
      (node (ref "U$11") (pin "P$1") (pinfunction "B1_P$1") (pintype "bidirectional"))
      (node (ref "U$11") (pin "P$3") (pinfunction "B3_P$3") (pintype "bidirectional"))
      (node (ref "U$6") (pin "P$3") (pinfunction "P$3_P$3") (pintype "bidirectional"))
    )
    (net (code "8") (name "BRAKE_RETURN") (class "Default")
      (node (ref "U$11") (pin "P$2") (pinfunction "B2_P$2") (pintype "bidirectional"))
      (node (ref "U$11") (pin "P$4") (pinfunction "B4_P$4") (pintype "bidirectional"))
      (node (ref "U$6") (pin "P$4") (pinfunction "P$4_P$4") (pintype "bidirectional"))
    )
    (net (code "9") (name "BRAKE_SIGNAL") (class "Default")
      (node (ref "RELAY1") (pin "P$5") (pinfunction "A2_P$5") (pintype "bidirectional"))
    )
    (net (code "10") (name "CONSOLE_RS485+") (class "Default")
      (node (ref "CPU1") (pin "P$J11-9") (pinfunction "J11_9_485+_P$J11-9") (pintype "bidirectional"))
      (node (ref "U$21") (pin "P$2") (pinfunction "LT_P$2") (pintype "bidirectional"))
    )
    (net (code "11") (name "CONSOLE_RS485-") (class "Default")
      (node (ref "CPU1") (pin "P$J11-4") (pinfunction "J11_4_485-_P$J11-4") (pintype "bidirectional"))
      (node (ref "U$21") (pin "P$1") (pinfunction "LB_P$1") (pintype "bidirectional"))
    )
    (net (code "12") (name "CONTACTOR_CONTROL") (class "Default")
      (node (ref "CONT1") (pin "P$9") (pinfunction "A1_P$9") (pintype "bidirectional"))
      (node (ref "RELAY2") (pin "P$1") (pinfunction "11_P$1") (pintype "bidirectional"))
    )
    (net (code "13") (name "DC_COMMON") (class "Default")
      (node (ref "CPU1") (pin "P$J12-1") (pinfunction "J12_1_AGND_P$J12-1") (pintype "bidirectional"))
      (node (ref "CPU1") (pin "P$J3-5") (pinfunction "J3_5_GND_P$J3-5") (pintype "bidirectional"))
      (node (ref "CPU1") (pin "P$J5-3") (pinfunction "J5_3_GND_P$J5-3") (pintype "bidirectional"))
      (node (ref "DISPLAY1") (pin "P$4") (pinfunction "GND_B_P$4") (pintype "bidirectional"))
      (node (ref "HALL") (pin "P$2") (pinfunction "GND(BK)_P$2") (pintype "bidirectional"))
      (node (ref "JOYSTICK") (pin "P$3") (pinfunction "GND_P$3") (pintype "bidirectional"))
      (node (ref "PS1") (pin "P$4") (pinfunction "4-(V-)_P$4") (pintype "bidirectional"))
      (node (ref "PS2") (pin "P$4") (pinfunction "GND1_P$4") (pintype "bidirectional"))
      (node (ref "PS2") (pin "P$5") (pinfunction "GND2_P$5") (pintype "bidirectional"))
      (node (ref "R1") (pin "P$1") (pinfunction "1_P$1") (pintype "passive"))
      (node (ref "R2") (pin "2") (pinfunction "2_2") (pintype "passive"))
      (node (ref "RELAY2") (pin "P$5") (pinfunction "A2_P$5") (pintype "bidirectional"))
      (node (ref "U$26") (pin "P$3") (pinfunction "RB_P$3") (pintype "bidirectional"))
      (node (ref "U$27") (pin "P$1") (pinfunction "LB_P$1") (pintype "bidirectional"))
      (node (ref "U$27") (pin "P$3") (pinfunction "RB_P$3") (pintype "bidirectional"))
      (node (ref "U$28") (pin "P$1") (pinfunction "LB_P$1") (pintype "bidirectional"))
      (node (ref "U$29") (pin "P$3") (pinfunction "RB_P$3") (pintype "bidirectional"))
      (node (ref "U$3") (pin "P$6") (pinfunction "P$6_P$6") (pintype "bidirectional"))
      (node (ref "U$31") (pin "P$1") (pinfunction "LB_P$1") (pintype "bidirectional"))
      (node (ref "U$31") (pin "P$3") (pinfunction "RB_P$3") (pintype "bidirectional"))
      (node (ref "U$32") (pin "P$1") (pinfunction "LB_P$1") (pintype "bidirectional"))
      (node (ref "U$32") (pin "P$3") (pinfunction "RB_P$3") (pintype "bidirectional"))
      (node (ref "U$33") (pin "P$3") (pinfunction "RB_P$3") (pintype "bidirectional"))
      (node (ref "U$34") (pin "P$1") (pinfunction "LB_P$1") (pintype "bidirectional"))
      (node (ref "U$35") (pin "P$1") (pinfunction "LB_P$1") (pintype "bidirectional"))
      (node (ref "U$8") (pin "P$1") (pinfunction "LB_P$1") (pintype "bidirectional"))
      (node (ref "U$8") (pin "P$3") (pinfunction "RB_P$3") (pintype "bidirectional"))
    )
    (net (code "14") (name "DISPLAY_RS232_RX") (class "Default")
      (node (ref "DISPLAY1") (pin "P$5") (pinfunction "RS232_TX_P$5") (pintype "bidirectional"))
      (node (ref "U$19") (pin "P$2") (pinfunction "LT_P$2") (pintype "bidirectional"))
      (node (ref "U$19") (pin "P$4") (pinfunction "RT_P$4") (pintype "bidirectional"))
    )
    (net (code "15") (name "DISPLAY_RS232_TX") (class "Default")
      (node (ref "CPU1") (pin "P$J11-1") (pinfunction "J11_1_PD6_TXE_P$J11-1") (pintype "bidirectional"))
    )
    (net (code "16") (name "DRIVE_24VDC") (class "Default")
      (node (ref "CPU1") (pin "P$J3-10") (pinfunction "J3_10_+K1_P$J3-10") (pintype "bidirectional"))
      (node (ref "U$27") (pin "P$2") (pinfunction "LT_P$2") (pintype "bidirectional"))
      (node (ref "U$27") (pin "P$4") (pinfunction "RT_P$4") (pintype "bidirectional"))
    )
    (net (code "17") (name "DRIVE_ALARM") (class "Default")
      (node (ref "CPU1") (pin "P$J1-9") (pinfunction "J1_9_DIO16_P$J1-9") (pintype "bidirectional"))
      (node (ref "U$23") (pin "P$2") (pinfunction "LT_P$2") (pintype "bidirectional"))
      (node (ref "U$23") (pin "P$4") (pinfunction "RT_P$4") (pintype "bidirectional"))
    )
    (net (code "18") (name "DRIVE_FWD") (class "Default")
      (node (ref "CPU1") (pin "P$J3-1") (pinfunction "J3_1_HOUT1_P$J3-1") (pintype "bidirectional"))
      (node (ref "U$22") (pin "P$2") (pinfunction "LT_P$2") (pintype "bidirectional"))
      (node (ref "U$22") (pin "P$4") (pinfunction "RT_P$4") (pintype "bidirectional"))
    )
    (net (code "19") (name "DRIVE_REV") (class "Default")
      (node (ref "CPU1") (pin "P$J3-4") (pinfunction "J3_4_HOUT3_P$J3-4") (pintype "bidirectional"))
      (node (ref "U$22") (pin "P$1") (pinfunction "LB_P$1") (pintype "bidirectional"))
      (node (ref "U$22") (pin "P$3") (pinfunction "RB_P$3") (pintype "bidirectional"))
    )
    (net (code "20") (name "DRIVE_SIGNAL") (class "Default")
      (node (ref "CPU1") (pin "P$J12-13") (pinfunction "J12_13_AOUT0_P$J12-13") (pintype "bidirectional"))
      (node (ref "U$23") (pin "P$1") (pinfunction "LB_P$1") (pintype "bidirectional"))
      (node (ref "U$23") (pin "P$3") (pinfunction "RB_P$3") (pintype "bidirectional"))
    )
    (net (code "21") (name "ESTOP_SIGNAL") (class "Default")
      (node (ref "CPU1") (pin "P$J1-1") (pinfunction "J1_1_DIO23_P$J1-1") (pintype "bidirectional"))
      (node (ref "R1") (pin "P$2") (pinfunction "2_P$2") (pintype "passive"))
      (node (ref "RELAY2") (pin "P$4") (pinfunction "A1_P$4") (pintype "bidirectional"))
      (node (ref "U$3") (pin "P$3") (pinfunction "P$3_P$3") (pintype "bidirectional"))
      (node (ref "U$3") (pin "P$4") (pinfunction "P$4_P$4") (pintype "bidirectional"))
      (node (ref "U$3") (pin "P$5") (pinfunction "P$5_P$5") (pintype "bidirectional"))
      (node (ref "U$4") (pin "P$2") (pinfunction "LT_P$2") (pintype "bidirectional"))
      (node (ref "U$4") (pin "P$4") (pinfunction "RT_P$4") (pintype "bidirectional"))
    )
    (net (code "22") (name "HALL_EFFECT_SIGNAL") (class "Default")
      (node (ref "CPU1") (pin "P$J2-4") (pinfunction "J2_4_DIO25_P$J2-4") (pintype "bidirectional"))
      (node (ref "HALL") (pin "P$3") (pinfunction "SIG(GN)_P$3") (pintype "bidirectional"))
      (node (ref "U$25") (pin "P$2") (pinfunction "LT_P$2") (pintype "bidirectional"))
      (node (ref "U$25") (pin "P$4") (pinfunction "RT_P$4") (pintype "bidirectional"))
    )
    (net (code "23") (name "HBU_N") (class "Default")
      (node (ref "HBU") (pin "P$11") (pinfunction "P$11_P$11") (pintype "bidirectional"))
      (node (ref "VFD") (pin "P$29") (pinfunction "P$29_P$29") (pintype "bidirectional"))
    )
    (net (code "24") (name "HBU_P") (class "Default")
      (node (ref "HBU") (pin "P$10") (pinfunction "P$10_P$10") (pintype "bidirectional"))
      (node (ref "VFD") (pin "P$28") (pinfunction "P$28_P$28") (pintype "bidirectional"))
    )
    (net (code "25") (name "HBU_P1") (class "Default")
      (node (ref "DBR1") (pin "2") (pinfunction "2_2") (pintype "passive"))
      (node (ref "DBR2") (pin "2") (pinfunction "2_2") (pintype "passive"))
      (node (ref "HBU") (pin "P$8") (pinfunction "P$8_P$8") (pintype "bidirectional"))
    )
    (net (code "26") (name "HBU_P2") (class "Default")
      (node (ref "DBR1") (pin "1") (pinfunction "1_1") (pintype "passive"))
      (node (ref "DBR2") (pin "1") (pinfunction "1_1") (pintype "passive"))
      (node (ref "HBU") (pin "P$9") (pinfunction "P$9_P$9") (pintype "bidirectional"))
    )
    (net (code "27") (name "JOG_LEFT_SIGNAL") (class "Default")
      (node (ref "CPU1") (pin "P$J1-3") (pinfunction "J1_3_DIO19_P$J1-3") (pintype "bidirectional"))
      (node (ref "U$1") (pin "P$2") (pinfunction "LT_P$2") (pintype "bidirectional"))
    )
    (net (code "28") (name "JOG_RIGHT_SIGNAL") (class "Default")
      (node (ref "CPU1") (pin "P$J1-4") (pinfunction "J1_4_DIO17_P$J1-4") (pintype "bidirectional"))
      (node (ref "U$1") (pin "P$1") (pinfunction "LB_P$1") (pintype "bidirectional"))
    )
    (net (code "29") (name "JOYSTICK_FORWARD_SIGNAL") (class "Default")
      (node (ref "CPU1") (pin "P$J1-7") (pinfunction "J1_7_DIO20_P$J1-7") (pintype "bidirectional"))
      (node (ref "JOYSTICK") (pin "P$2") (pinfunction "B_P$2") (pintype "bidirectional"))
      (node (ref "U$16") (pin "P$1") (pinfunction "LB_P$1") (pintype "bidirectional"))
      (node (ref "U$16") (pin "P$3") (pinfunction "RB_P$3") (pintype "bidirectional"))
    )
    (net (code "30") (name "JOYSTICK_REVERSE_SIGNAL") (class "Default")
      (node (ref "CPU1") (pin "P$J1-8") (pinfunction "J1_8_DIO18_P$J1-8") (pintype "bidirectional"))
      (node (ref "JOYSTICK") (pin "P$1") (pinfunction "A_P$1") (pintype "bidirectional"))
      (node (ref "U$17") (pin "P$1") (pinfunction "LB_P$1") (pintype "bidirectional"))
      (node (ref "U$17") (pin "P$3") (pinfunction "RB_P$3") (pintype "bidirectional"))
    )
    (net (code "31") (name "JOYSTICK_SIGNAL") (class "Default")
      (node (ref "CPU1") (pin "P$J12-12") (pinfunction "J12_12_AIN0_P$J12-12") (pintype "bidirectional"))
      (node (ref "JOYSTICK") (pin "P$4") (pinfunction "SIG_P$4") (pintype "bidirectional"))
      (node (ref "U$16") (pin "P$2") (pinfunction "LT_P$2") (pintype "bidirectional"))
      (node (ref "U$16") (pin "P$4") (pinfunction "RT_P$4") (pintype "bidirectional"))
    )
    (net (code "32") (name "MAINS_L1") (class "Default")
      (node (ref "DS") (pin "P$3") (pinfunction "P$3_P$3") (pintype "bidirectional"))
      (node (ref "DS") (pin "P$4") (pinfunction "P$4_P$4") (pintype "bidirectional"))
      (node (ref "FUSE1") (pin "P$2") (pinfunction "P$2_P$2") (pintype "bidirectional"))
    )
    (net (code "33") (name "MAINS_L1_FUSED") (class "Default")
      (node (ref "CONT1") (pin "P$1") (pinfunction "1L1_P$1") (pintype "bidirectional"))
      (node (ref "CONT1") (pin "P$2") (pinfunction "2T1_P$2") (pintype "bidirectional"))
      (node (ref "FUSE1") (pin "P$3") (pinfunction "P$3_P$3") (pintype "bidirectional"))
      (node (ref "PS1") (pin "P$1") (pinfunction "1-AC/L_P$1") (pintype "bidirectional"))
      (node (ref "RELAY1") (pin "P$3") (pinfunction "14_P$3") (pintype "bidirectional"))
      (node (ref "RELAY2") (pin "P$3") (pinfunction "14_P$3") (pintype "bidirectional"))
      (node (ref "VFD") (pin "P$23") (pinfunction "P$23_P$23") (pintype "bidirectional"))
    )
    (net (code "34") (name "MAINS_L2") (class "Default")
      (node (ref "DS") (pin "P$2") (pinfunction "P$2_P$2") (pintype "bidirectional"))
      (node (ref "DS") (pin "P$5") (pinfunction "P$5_P$5") (pintype "bidirectional"))
      (node (ref "FUSE1") (pin "P$1") (pinfunction "P$1_P$1") (pintype "bidirectional"))
    )
    (net (code "35") (name "MAINS_L2_FUSED") (class "Default")
      (node (ref "CONT1") (pin "P$10") (pinfunction "A2_P$10") (pintype "bidirectional"))
      (node (ref "CONT1") (pin "P$3") (pinfunction "3L2_P$3") (pintype "bidirectional"))
      (node (ref "CONT1") (pin "P$4") (pinfunction "4T2_P$4") (pintype "bidirectional"))
      (node (ref "FUSE1") (pin "P$4") (pinfunction "P$4_P$4") (pintype "bidirectional"))
      (node (ref "PS1") (pin "P$2") (pinfunction "2-AC/N_P$2") (pintype "bidirectional"))
      (node (ref "U$6") (pin "P$1") (pinfunction "P$1_P$1") (pintype "bidirectional"))
      (node (ref "VFD") (pin "P$24") (pinfunction "P$24_P$24") (pintype "bidirectional"))
    )
    (net (code "36") (name "MAINS_L3") (class "Default")
      (node (ref "DS") (pin "P$1") (pinfunction "P$1_P$1") (pintype "bidirectional"))
      (node (ref "DS") (pin "P$6") (pinfunction "P$6_P$6") (pintype "bidirectional"))
      (node (ref "FUSE1") (pin "P$5") (pinfunction "P$5_P$5") (pintype "bidirectional"))
    )
    (net (code "37") (name "MAINS_L3_FUSED") (class "Default")
      (node (ref "CONT1") (pin "P$5") (pinfunction "5L3_P$5") (pintype "bidirectional"))
      (node (ref "CONT1") (pin "P$6") (pinfunction "6T3_P$6") (pintype "bidirectional"))
      (node (ref "FUSE1") (pin "P$6") (pinfunction "P$6_P$6") (pintype "bidirectional"))
      (node (ref "VFD") (pin "P$25") (pinfunction "P$25_P$25") (pintype "bidirectional"))
    )
    (net (code "38") (name "MAINS_PE") (class "Default")
      (node (ref "DS") (pin "P$7") (pinfunction "P$7_P$7") (pintype "bidirectional"))
      (node (ref "DS") (pin "P$8") (pinfunction "P$8_P$8") (pintype "bidirectional"))
    )
    (net (code "39") (name "MOTOR_PE") (class "Default")
      (node (ref "U$11") (pin "P$14") (pinfunction "GND_P$14") (pintype "bidirectional"))
    )
    (net (code "40") (name "MOTOR_U") (class "Default")
      (node (ref "U$11") (pin "P$11") (pinfunction "T7_P$11") (pintype "bidirectional"))
      (node (ref "U$11") (pin "P$5") (pinfunction "T1_P$5") (pintype "bidirectional"))
      (node (ref "VFD") (pin "P$32") (pinfunction "P$32_P$32") (pintype "bidirectional"))
    )
    (net (code "41") (name "MOTOR_V") (class "Default")
      (node (ref "U$11") (pin "P$12") (pinfunction "T8_P$12") (pintype "bidirectional"))
      (node (ref "U$11") (pin "P$6") (pinfunction "T2_P$6") (pintype "bidirectional"))
      (node (ref "VFD") (pin "P$31") (pinfunction "P$31_P$31") (pintype "bidirectional"))
    )
    (net (code "42") (name "MOTOR_W") (class "Default")
      (node (ref "U$11") (pin "P$13") (pinfunction "T9_P$13") (pintype "bidirectional"))
      (node (ref "U$11") (pin "P$7") (pinfunction "T3_P$7") (pintype "bidirectional"))
      (node (ref "VFD") (pin "P$30") (pinfunction "P$30_P$30") (pintype "bidirectional"))
    )
    (net (code "43") (name "N$1") (class "Default")
      (node (ref "U$5") (pin "P$11") (pinfunction "D-_P$11") (pintype "bidirectional"))
    )
    (net (code "44") (name "N$2") (class "Default")
      (node (ref "U$5") (pin "P$10") (pinfunction "D+_P$10") (pintype "bidirectional"))
    )
    (net (code "45") (name "N$4") (class "Default")
      (node (ref "U$5") (pin "P$12") (pinfunction "GND_P$12") (pintype "bidirectional"))
    )
    (net (code "46") (name "Net-(U$11-T4)") (class "Default")
      (node (ref "U$11") (pin "P$10") (pinfunction "T6_P$10") (pintype "bidirectional"))
      (node (ref "U$11") (pin "P$8") (pinfunction "T4_P$8") (pintype "bidirectional"))
      (node (ref "U$11") (pin "P$9") (pinfunction "T5_P$9") (pintype "bidirectional"))
    )
    (net (code "47") (name "PE") (class "Default")
      (node (ref "HBU") (pin "P$7") (pinfunction "P$7_P$7") (pintype "bidirectional"))
      (node (ref "PS1") (pin "P$3") (pinfunction "3-PE_P$3") (pintype "bidirectional"))
      (node (ref "VFD") (pin "P$34") (pinfunction "P$34_P$34") (pintype "bidirectional"))
    )
    (net (code "48") (name "PROX_LEFT_SIGNAL") (class "Default")
      (node (ref "CPU1") (pin "P$J2-2") (pinfunction "J2_2_DIO29_P$J2-2") (pintype "bidirectional"))
      (node (ref "U$24") (pin "P$1") (pinfunction "LB_P$1") (pintype "bidirectional"))
    )
    (net (code "49") (name "PROX_RIGHT_SIGNAL") (class "Default")
      (node (ref "CPU1") (pin "P$J2-1") (pinfunction "J2_1_DIO31_P$J2-1") (pintype "bidirectional"))
      (node (ref "U$24") (pin "P$2") (pinfunction "LT_P$2") (pintype "bidirectional"))
    )
    (net (code "50") (name "RADIO_RS232_RX") (class "Default")
      (node (ref "CPU1") (pin "P$J11-7") (pinfunction "J11_7_PD3_RXF_P$J11-7") (pintype "bidirectional"))
      (node (ref "U$20") (pin "P$1") (pinfunction "LB_P$1") (pintype "bidirectional"))
    )
    (net (code "51") (name "RADIO_RS232_TX") (class "Default")
      (node (ref "CPU1") (pin "P$J11-2") (pinfunction "J11_2_PD2_TXF_P$J11-2") (pintype "bidirectional"))
      (node (ref "U$20") (pin "P$2") (pinfunction "LT_P$2") (pintype "bidirectional"))
    )
    (net (code "52") (name "REMOTE_SIGNAL") (class "Default")
      (node (ref "CPU1") (pin "P$J2-6") (pinfunction "J2_6_DIO30_P$J2-6") (pintype "bidirectional"))
      (node (ref "U$17") (pin "P$2") (pinfunction "LT_P$2") (pintype "bidirectional"))
    )
    (net (code "53") (name "RESET_SIGNAL") (class "Default")
      (node (ref "CPU1") (pin "P$J1-6") (pinfunction "J1_6_DIO22_P$J1-6") (pintype "bidirectional"))
      (node (ref "RESET") (pin "P$1") (pinfunction "P$1_P$1") (pintype "bidirectional"))
      (node (ref "U$18") (pin "P$2") (pinfunction "LT_P$2") (pintype "bidirectional"))
      (node (ref "U$18") (pin "P$4") (pinfunction "RT_P$4") (pintype "bidirectional"))
    )
    (net (code "54") (name "RS485+") (class "Default")
      (node (ref "U$21") (pin "P$4") (pinfunction "RT_P$4") (pintype "bidirectional"))
    )
    (net (code "55") (name "RS485-") (class "Default")
      (node (ref "U$21") (pin "P$3") (pinfunction "RB_P$3") (pintype "bidirectional"))
    )
    (net (code "56") (name "SPEED_SIGNAL") (class "Default")
      (node (ref "CPU1") (pin "P$J2-7") (pinfunction "J2_7_DIO28_P$J2-7") (pintype "bidirectional"))
      (node (ref "U$18") (pin "P$1") (pinfunction "LB_P$1") (pintype "bidirectional"))
    )
    (net (code "57") (name "STEPPER_DIR") (class "Default")
      (node (ref "CPU1") (pin "P$J4-4") (pinfunction "J4_4_HOUT7_P$J4-4") (pintype "bidirectional"))
      (node (ref "U$2") (pin "P$1") (pinfunction "LB_P$1") (pintype "bidirectional"))
    )
    (net (code "58") (name "STEPPER_STEP") (class "Default")
      (node (ref "CPU1") (pin "P$J4-1") (pinfunction "J4_1_HOUT5_P$J4-1") (pintype "bidirectional"))
      (node (ref "U$2") (pin "P$2") (pinfunction "LT_P$2") (pintype "bidirectional"))
    )
    (net (code "59") (name "THERMISTOR.SIGNAL") (class "Default")
      (node (ref "CPU1") (pin "P$J12-2") (pinfunction "J12_2_AIN6_P$J12-2") (pintype "bidirectional"))
      (node (ref "R2") (pin "1") (pinfunction "1_1") (pintype "passive"))
      (node (ref "U$14") (pin "P$1") (pinfunction "P$1_P$1") (pintype "bidirectional"))
      (node (ref "U$4") (pin "P$1") (pinfunction "LB_P$1") (pintype "bidirectional"))
      (node (ref "U$4") (pin "P$3") (pinfunction "RB_P$3") (pintype "bidirectional"))
    )
    (net (code "60") (name "USER_INPUT_1") (class "Default")
      (node (ref "CPU1") (pin "P$J10-1") (pinfunction "J10_1_DIO7_P$J10-1") (pintype "bidirectional"))
    )
    (net (code "61") (name "USER_INPUT_2") (class "Default")
      (node (ref "CPU1") (pin "P$J10-2") (pinfunction "J10_2_DIO5_P$J10-2") (pintype "bidirectional"))
    )
    (net (code "62") (name "USER_INPUT_3") (class "Default")
      (node (ref "CPU1") (pin "P$J10-3") (pinfunction "J10_3_DIO3_P$J10-3") (pintype "bidirectional"))
    )
    (net (code "63") (name "USER_INPUT_4") (class "Default")
      (node (ref "CPU1") (pin "P$J10-4") (pinfunction "J10_4_DIO1_P$J10-4") (pintype "bidirectional"))
    )
    (net (code "64") (name "USER_INPUT_5") (class "Default")
      (node (ref "CPU1") (pin "P$J10-6") (pinfunction "J10_6_DIO6_P$J10-6") (pintype "bidirectional"))
    )
    (net (code "65") (name "unconnected-(CONT1-13NO-PadP$7)") (class "Default")
      (node (ref "CONT1") (pin "P$7") (pinfunction "13NO_P$7") (pintype "bidirectional"))
    )
    (net (code "66") (name "unconnected-(CONT1-14N0-PadP$8)") (class "Default")
      (node (ref "CONT1") (pin "P$8") (pinfunction "14N0_P$8") (pintype "bidirectional"))
    )
    (net (code "67") (name "unconnected-(CPU1-J1_2_DIO21-PadP$J1-2)") (class "Default")
      (node (ref "CPU1") (pin "P$J1-2") (pinfunction "J1_2_DIO21_P$J1-2") (pintype "bidirectional"))
    )
    (net (code "68") (name "unconnected-(CPU1-J1_5_GND-PadP$J1-5)") (class "Default")
      (node (ref "CPU1") (pin "P$J1-5") (pinfunction "J1_5_GND_P$J1-5") (pintype "bidirectional"))
    )
    (net (code "69") (name "unconnected-(CPU1-J1_10_+KC-PadP$J1-10)") (class "Default")
      (node (ref "CPU1") (pin "P$J1-10") (pinfunction "J1_10_+KC_P$J1-10") (pintype "bidirectional"))
    )
    (net (code "70") (name "unconnected-(CPU1-J2_3_DIO27-PadP$J2-3)") (class "Default")
      (node (ref "CPU1") (pin "P$J2-3") (pinfunction "J2_3_DIO27_P$J2-3") (pintype "bidirectional"))
    )
    (net (code "71") (name "unconnected-(CPU1-J2_5_GND-PadP$J2-5)") (class "Default")
      (node (ref "CPU1") (pin "P$J2-5") (pinfunction "J2_5_GND_P$J2-5") (pintype "bidirectional"))
    )
    (net (code "72") (name "unconnected-(CPU1-J2_8_DIO26-PadP$J2-8)") (class "Default")
      (node (ref "CPU1") (pin "P$J2-8") (pinfunction "J2_8_DIO26_P$J2-8") (pintype "bidirectional"))
    )
    (net (code "73") (name "unconnected-(CPU1-J2_9_DIO24-PadP$J2-9)") (class "Default")
      (node (ref "CPU1") (pin "P$J2-9") (pinfunction "J2_9_DIO24_P$J2-9") (pintype "bidirectional"))
    )
    (net (code "74") (name "unconnected-(CPU1-J2_10_+KD-PadP$J2-10)") (class "Default")
      (node (ref "CPU1") (pin "P$J2-10") (pinfunction "J2_10_+KD_P$J2-10") (pintype "bidirectional"))
    )
    (net (code "75") (name "unconnected-(CPU1-J3_2_GND-PadP$J3-2)") (class "Default")
      (node (ref "CPU1") (pin "P$J3-2") (pinfunction "J3_2_GND_P$J3-2") (pintype "bidirectional"))
    )
    (net (code "76") (name "unconnected-(CPU1-J3_6_HOUT0-PadP$J3-6)") (class "Default")
      (node (ref "CPU1") (pin "P$J3-6") (pinfunction "J3_6_HOUT0_P$J3-6") (pintype "bidirectional"))
    )
    (net (code "77") (name "unconnected-(CPU1-J3_7_+K1-PadP$J3-7)") (class "Default")
      (node (ref "CPU1") (pin "P$J3-7") (pinfunction "J3_7_+K1_P$J3-7") (pintype "bidirectional"))
    )
    (net (code "78") (name "unconnected-(CPU1-J3_9_HOUT2-PadP$J3-9)") (class "Default")
      (node (ref "CPU1") (pin "P$J3-9") (pinfunction "J3_9_HOUT2_P$J3-9") (pintype "bidirectional"))
    )
    (net (code "79") (name "unconnected-(CPU1-J4_2_GND-PadP$J4-2)") (class "Default")
      (node (ref "CPU1") (pin "P$J4-2") (pinfunction "J4_2_GND_P$J4-2") (pintype "bidirectional"))
    )
    (net (code "80") (name "unconnected-(CPU1-J4_5_GND-PadP$J4-5)") (class "Default")
      (node (ref "CPU1") (pin "P$J4-5") (pinfunction "J4_5_GND_P$J4-5") (pintype "bidirectional"))
    )
    (net (code "81") (name "unconnected-(CPU1-J4_6_HOUT4-PadP$J4-6)") (class "Default")
      (node (ref "CPU1") (pin "P$J4-6") (pinfunction "J4_6_HOUT4_P$J4-6") (pintype "bidirectional"))
    )
    (net (code "82") (name "unconnected-(CPU1-J4_7_+K2-PadP$J4-7)") (class "Default")
      (node (ref "CPU1") (pin "P$J4-7") (pinfunction "J4_7_+K2_P$J4-7") (pintype "bidirectional"))
    )
    (net (code "83") (name "unconnected-(CPU1-J4_9_HOUT6-PadP$J4-9)") (class "Default")
      (node (ref "CPU1") (pin "P$J4-9") (pinfunction "J4_9_HOUT6_P$J4-9") (pintype "bidirectional"))
    )
    (net (code "84") (name "unconnected-(CPU1-J7_1_+RAW-PadP$J7-1)") (class "Default")
      (node (ref "CPU1") (pin "P$J7-1") (pinfunction "J7_1_+RAW_P$J7-1") (pintype "bidirectional"))
    )
    (net (code "85") (name "unconnected-(CPU1-J7_2_+RAW-PadP$J7-2)") (class "Default")
      (node (ref "CPU1") (pin "P$J7-2") (pinfunction "J7_2_+RAW_P$J7-2") (pintype "bidirectional"))
    )
    (net (code "86") (name "unconnected-(CPU1-J7_3_+5V-PadP$J7-3)") (class "Default")
      (node (ref "CPU1") (pin "P$J7-3") (pinfunction "J7_3_+5V_P$J7-3") (pintype "bidirectional"))
    )
    (net (code "87") (name "unconnected-(CPU1-J7_4_GND-PadP$J7-4)") (class "Default")
      (node (ref "CPU1") (pin "P$J7-4") (pinfunction "J7_4_GND_P$J7-4") (pintype "bidirectional"))
    )
    (net (code "88") (name "unconnected-(CPU1-J7_5_GND-PadP$J7-5)") (class "Default")
      (node (ref "CPU1") (pin "P$J7-5") (pinfunction "J7_5_GND_P$J7-5") (pintype "bidirectional"))
    )
    (net (code "89") (name "unconnected-(CPU1-J7_6_+5V-PadP$J7-6)") (class "Default")
      (node (ref "CPU1") (pin "P$J7-6") (pinfunction "J7_6_+5V_P$J7-6") (pintype "bidirectional"))
    )
    (net (code "90") (name "unconnected-(CPU1-J9_1_DIO15-PadP$J9-1)") (class "Default")
      (node (ref "CPU1") (pin "P$J9-1") (pinfunction "J9_1_DIO15_P$J9-1") (pintype "bidirectional"))
    )
    (net (code "91") (name "unconnected-(CPU1-J9_2_DIO13-PadP$J9-2)") (class "Default")
      (node (ref "CPU1") (pin "P$J9-2") (pinfunction "J9_2_DIO13_P$J9-2") (pintype "bidirectional"))
    )
    (net (code "92") (name "unconnected-(CPU1-J9_3_DIO11-PadP$J9-3)") (class "Default")
      (node (ref "CPU1") (pin "P$J9-3") (pinfunction "J9_3_DIO11_P$J9-3") (pintype "bidirectional"))
    )
    (net (code "93") (name "unconnected-(CPU1-J9_4_DIO9-PadP$J9-4)") (class "Default")
      (node (ref "CPU1") (pin "P$J9-4") (pinfunction "J9_4_DIO9_P$J9-4") (pintype "bidirectional"))
    )
    (net (code "94") (name "unconnected-(CPU1-J9_5_GND-PadP$J9-5)") (class "Default")
      (node (ref "CPU1") (pin "P$J9-5") (pinfunction "J9_5_GND_P$J9-5") (pintype "bidirectional"))
    )
    (net (code "95") (name "unconnected-(CPU1-J9_6_DIO14-PadP$J9-6)") (class "Default")
      (node (ref "CPU1") (pin "P$J9-6") (pinfunction "J9_6_DIO14_P$J9-6") (pintype "bidirectional"))
    )
    (net (code "96") (name "unconnected-(CPU1-J9_7_DIO12-PadP$J9-7)") (class "Default")
      (node (ref "CPU1") (pin "P$J9-7") (pinfunction "J9_7_DIO12_P$J9-7") (pintype "bidirectional"))
    )
    (net (code "97") (name "unconnected-(CPU1-J9_8_DIO10-PadP$J9-8)") (class "Default")
      (node (ref "CPU1") (pin "P$J9-8") (pinfunction "J9_8_DIO10_P$J9-8") (pintype "bidirectional"))
    )
    (net (code "98") (name "unconnected-(CPU1-J9_9_DIO8-PadP$J9-9)") (class "Default")
      (node (ref "CPU1") (pin "P$J9-9") (pinfunction "J9_9_DIO8_P$J9-9") (pintype "bidirectional"))
    )
    (net (code "99") (name "unconnected-(CPU1-J9_10_+KB-PadP$J9-10)") (class "Default")
      (node (ref "CPU1") (pin "P$J9-10") (pinfunction "J9_10_+KB_P$J9-10") (pintype "bidirectional"))
    )
    (net (code "100") (name "unconnected-(CPU1-J10_5_GND-PadP$J10-5)") (class "Default")
      (node (ref "CPU1") (pin "P$J10-5") (pinfunction "J10_5_GND_P$J10-5") (pintype "bidirectional"))
    )
    (net (code "101") (name "unconnected-(CPU1-J10_7_DIO4-PadP$J10-7)") (class "Default")
      (node (ref "CPU1") (pin "P$J10-7") (pinfunction "J10_7_DIO4_P$J10-7") (pintype "bidirectional"))
    )
    (net (code "102") (name "unconnected-(CPU1-J10_8_DIO2-PadP$J10-8)") (class "Default")
      (node (ref "CPU1") (pin "P$J10-8") (pinfunction "J10_8_DIO2_P$J10-8") (pintype "bidirectional"))
    )
    (net (code "103") (name "unconnected-(CPU1-J10_9_DIO0-PadP$J10-9)") (class "Default")
      (node (ref "CPU1") (pin "P$J10-9") (pinfunction "J10_9_DIO0_P$J10-9") (pintype "bidirectional"))
    )
    (net (code "104") (name "unconnected-(CPU1-J10_10_+KA-PadP$J10-10)") (class "Default")
      (node (ref "CPU1") (pin "P$J10-10") (pinfunction "J10_10_+KA_P$J10-10") (pintype "bidirectional"))
    )
    (net (code "105") (name "unconnected-(CPU1-J11_3_GND-PadP$J11-3)") (class "Default")
      (node (ref "CPU1") (pin "P$J11-3") (pinfunction "J11_3_GND_P$J11-3") (pintype "bidirectional"))
    )
    (net (code "106") (name "unconnected-(CPU1-J11_5_GND-PadP$J11-5)") (class "Default")
      (node (ref "CPU1") (pin "P$J11-5") (pinfunction "J11_5_GND_P$J11-5") (pintype "bidirectional"))
    )
    (net (code "107") (name "unconnected-(CPU1-J11_6_PD7_RXE-PadP$J11-6)") (class "Default")
      (node (ref "CPU1") (pin "P$J11-6") (pinfunction "J11_6_PD7_RXE_P$J11-6") (pintype "bidirectional"))
    )
    (net (code "108") (name "unconnected-(CPU1-J11_8_GND-PadP$J11-8)") (class "Default")
      (node (ref "CPU1") (pin "P$J11-8") (pinfunction "J11_8_GND_P$J11-8") (pintype "bidirectional"))
    )
    (net (code "109") (name "unconnected-(CPU1-J12_3_AIN4-PadP$J12-3)") (class "Default")
      (node (ref "CPU1") (pin "P$J12-3") (pinfunction "J12_3_AIN4_P$J12-3") (pintype "bidirectional"))
    )
    (net (code "110") (name "unconnected-(CPU1-J12_4_AIN3-PadP$J12-4)") (class "Default")
      (node (ref "CPU1") (pin "P$J12-4") (pinfunction "J12_4_AIN3_P$J12-4") (pintype "bidirectional"))
    )
    (net (code "111") (name "unconnected-(CPU1-J12_5_AIN1-PadP$J12-5)") (class "Default")
      (node (ref "CPU1") (pin "P$J12-5") (pinfunction "J12_5_AIN1_P$J12-5") (pintype "bidirectional"))
    )
    (net (code "112") (name "unconnected-(CPU1-J12_6_AGND-PadP$J12-6)") (class "Default")
      (node (ref "CPU1") (pin "P$J12-6") (pinfunction "J12_6_AGND_P$J12-6") (pintype "bidirectional"))
    )
    (net (code "113") (name "unconnected-(CPU1-J12_7_AOUT1-PadP$J12-7)") (class "Default")
      (node (ref "CPU1") (pin "P$J12-7") (pinfunction "J12_7_AOUT1_P$J12-7") (pintype "bidirectional"))
    )
    (net (code "114") (name "unconnected-(CPU1-J12_8_AIN7-PadP$J12-8)") (class "Default")
      (node (ref "CPU1") (pin "P$J12-8") (pinfunction "J12_8_AIN7_P$J12-8") (pintype "bidirectional"))
    )
    (net (code "115") (name "unconnected-(CPU1-J12_9_AIN5-PadP$J12-9)") (class "Default")
      (node (ref "CPU1") (pin "P$J12-9") (pinfunction "J12_9_AIN5_P$J12-9") (pintype "bidirectional"))
    )
    (net (code "116") (name "unconnected-(CPU1-J12_10_AGND-PadP$J12-10)") (class "Default")
      (node (ref "CPU1") (pin "P$J12-10") (pinfunction "J12_10_AGND_P$J12-10") (pintype "bidirectional"))
    )
    (net (code "117") (name "unconnected-(CPU1-J12_11_AIN2-PadP$J12-11)") (class "Default")
      (node (ref "CPU1") (pin "P$J12-11") (pinfunction "J12_11_AIN2_P$J12-11") (pintype "bidirectional"))
    )
    (net (code "118") (name "unconnected-(CPU1-J12_14_AGND-PadP$J12-14)") (class "Default")
      (node (ref "CPU1") (pin "P$J12-14") (pinfunction "J12_14_AGND_P$J12-14") (pintype "bidirectional"))
    )
    (net (code "119") (name "unconnected-(DISPLAY1-5V_A-PadP$1)") (class "Default")
      (node (ref "DISPLAY1") (pin "P$1") (pinfunction "5V_A_P$1") (pintype "bidirectional"))
    )
    (net (code "120") (name "unconnected-(DISPLAY1-GND_A-PadP$3)") (class "Default")
      (node (ref "DISPLAY1") (pin "P$3") (pinfunction "GND_A_P$3") (pintype "bidirectional"))
    )
    (net (code "121") (name "unconnected-(HBU-PadP$1)") (class "Default")
      (node (ref "HBU") (pin "P$1") (pinfunction "P$1_P$1") (pintype "bidirectional"))
    )
    (net (code "122") (name "unconnected-(HBU-PadP$2)") (class "Default")
      (node (ref "HBU") (pin "P$2") (pinfunction "P$2_P$2") (pintype "bidirectional"))
    )
    (net (code "123") (name "unconnected-(HBU-PadP$3)") (class "Default")
      (node (ref "HBU") (pin "P$3") (pinfunction "P$3_P$3") (pintype "bidirectional"))
    )
    (net (code "124") (name "unconnected-(HBU-PadP$4)") (class "Default")
      (node (ref "HBU") (pin "P$4") (pinfunction "P$4_P$4") (pintype "bidirectional"))
    )
    (net (code "125") (name "unconnected-(HBU-PadP$5)") (class "Default")
      (node (ref "HBU") (pin "P$5") (pinfunction "P$5_P$5") (pintype "bidirectional"))
    )
    (net (code "126") (name "unconnected-(HBU-PadP$6)") (class "Default")
      (node (ref "HBU") (pin "P$6") (pinfunction "P$6_P$6") (pintype "bidirectional"))
    )
    (net (code "127") (name "unconnected-(PS2-+5VDCB-PadP$2)") (class "Default")
      (node (ref "PS2") (pin "P$2") (pinfunction "+5VDCB_P$2") (pintype "bidirectional"))
    )
    (net (code "128") (name "unconnected-(RELAY1-12-PadP$2)") (class "Default")
      (node (ref "RELAY1") (pin "P$2") (pinfunction "12_P$2") (pintype "bidirectional"))
    )
    (net (code "129") (name "unconnected-(RELAY2-12-PadP$2)") (class "Default")
      (node (ref "RELAY2") (pin "P$2") (pinfunction "12_P$2") (pintype "bidirectional"))
    )
    (net (code "130") (name "unconnected-(U$1-RB-PadP$3)") (class "Default")
      (node (ref "U$1") (pin "P$3") (pinfunction "RB_P$3") (pintype "bidirectional"))
    )
    (net (code "131") (name "unconnected-(U$1-RT-PadP$4)") (class "Default")
      (node (ref "U$1") (pin "P$4") (pinfunction "RT_P$4") (pintype "bidirectional"))
    )
    (net (code "132") (name "unconnected-(U$2-RB-PadP$3)") (class "Default")
      (node (ref "U$2") (pin "P$3") (pinfunction "RB_P$3") (pintype "bidirectional"))
    )
    (net (code "133") (name "unconnected-(U$2-RT-PadP$4)") (class "Default")
      (node (ref "U$2") (pin "P$4") (pinfunction "RT_P$4") (pintype "bidirectional"))
    )
    (net (code "134") (name "unconnected-(U$5-1-PadP$1)") (class "Default")
      (node (ref "U$5") (pin "P$1") (pinfunction "1_P$1") (pintype "bidirectional"))
    )
    (net (code "135") (name "unconnected-(U$5-2-PadP$2)") (class "Default")
      (node (ref "U$5") (pin "P$2") (pinfunction "2_P$2") (pintype "bidirectional"))
    )
    (net (code "136") (name "unconnected-(U$5-3-PadP$3)") (class "Default")
      (node (ref "U$5") (pin "P$3") (pinfunction "3_P$3") (pintype "bidirectional"))
    )
    (net (code "137") (name "unconnected-(U$5-4-PadP$4)") (class "Default")
      (node (ref "U$5") (pin "P$4") (pinfunction "4_P$4") (pintype "bidirectional"))
    )
    (net (code "138") (name "unconnected-(U$5-5-PadP$5)") (class "Default")
      (node (ref "U$5") (pin "P$5") (pinfunction "5_P$5") (pintype "bidirectional"))
    )
    (net (code "139") (name "unconnected-(U$5-6-PadP$6)") (class "Default")
      (node (ref "U$5") (pin "P$6") (pinfunction "6_P$6") (pintype "bidirectional"))
    )
    (net (code "140") (name "unconnected-(U$5-7-PadP$7)") (class "Default")
      (node (ref "U$5") (pin "P$7") (pinfunction "7_P$7") (pintype "bidirectional"))
    )
    (net (code "141") (name "unconnected-(U$5-8-PadP$8)") (class "Default")
      (node (ref "U$5") (pin "P$8") (pinfunction "8_P$8") (pintype "bidirectional"))
    )
    (net (code "142") (name "unconnected-(U$5-9-PadP$9)") (class "Default")
      (node (ref "U$5") (pin "P$9") (pinfunction "9_P$9") (pintype "bidirectional"))
    )
    (net (code "143") (name "unconnected-(U$7-LB-PadP$1)") (class "Default")
      (node (ref "U$7") (pin "P$1") (pinfunction "LB_P$1") (pintype "bidirectional"))
    )
    (net (code "144") (name "unconnected-(U$7-LT-PadP$2)") (class "Default")
      (node (ref "U$7") (pin "P$2") (pinfunction "LT_P$2") (pintype "bidirectional"))
    )
    (net (code "145") (name "unconnected-(U$7-RB-PadP$3)") (class "Default")
      (node (ref "U$7") (pin "P$3") (pinfunction "RB_P$3") (pintype "bidirectional"))
    )
    (net (code "146") (name "unconnected-(U$7-RT-PadP$4)") (class "Default")
      (node (ref "U$7") (pin "P$4") (pinfunction "RT_P$4") (pintype "bidirectional"))
    )
    (net (code "147") (name "unconnected-(U$8-LT-PadP$2)") (class "Default")
      (node (ref "U$8") (pin "P$2") (pinfunction "LT_P$2") (pintype "bidirectional"))
    )
    (net (code "148") (name "unconnected-(U$9-PadP$1)") (class "Default")
      (node (ref "U$9") (pin "P$1") (pinfunction "P$1_P$1") (pintype "bidirectional"))
    )
    (net (code "149") (name "unconnected-(U$9-PadP$3)") (class "Default")
      (node (ref "U$9") (pin "P$3") (pinfunction "P$3_P$3") (pintype "bidirectional"))
    )
    (net (code "150") (name "unconnected-(U$10-PadP$1)") (class "Default")
      (node (ref "U$10") (pin "P$1") (pinfunction "P$1_P$1") (pintype "bidirectional"))
    )
    (net (code "151") (name "unconnected-(U$10-PadP$3)") (class "Default")
      (node (ref "U$10") (pin "P$3") (pinfunction "P$3_P$3") (pintype "bidirectional"))
    )
    (net (code "152") (name "unconnected-(U$17-RT-PadP$4)") (class "Default")
      (node (ref "U$17") (pin "P$4") (pinfunction "RT_P$4") (pintype "bidirectional"))
    )
    (net (code "153") (name "unconnected-(U$18-RB-PadP$3)") (class "Default")
      (node (ref "U$18") (pin "P$3") (pinfunction "RB_P$3") (pintype "bidirectional"))
    )
    (net (code "154") (name "unconnected-(U$19-LB-PadP$1)") (class "Default")
      (node (ref "U$19") (pin "P$1") (pinfunction "LB_P$1") (pintype "bidirectional"))
    )
    (net (code "155") (name "unconnected-(U$19-RB-PadP$3)") (class "Default")
      (node (ref "U$19") (pin "P$3") (pinfunction "RB_P$3") (pintype "bidirectional"))
    )
    (net (code "156") (name "unconnected-(U$20-RB-PadP$3)") (class "Default")
      (node (ref "U$20") (pin "P$3") (pinfunction "RB_P$3") (pintype "bidirectional"))
    )
    (net (code "157") (name "unconnected-(U$20-RT-PadP$4)") (class "Default")
      (node (ref "U$20") (pin "P$4") (pinfunction "RT_P$4") (pintype "bidirectional"))
    )
    (net (code "158") (name "unconnected-(U$24-RB-PadP$3)") (class "Default")
      (node (ref "U$24") (pin "P$3") (pinfunction "RB_P$3") (pintype "bidirectional"))
    )
    (net (code "159") (name "unconnected-(U$24-RT-PadP$4)") (class "Default")
      (node (ref "U$24") (pin "P$4") (pinfunction "RT_P$4") (pintype "bidirectional"))
    )
    (net (code "160") (name "unconnected-(U$25-LB-PadP$1)") (class "Default")
      (node (ref "U$25") (pin "P$1") (pinfunction "LB_P$1") (pintype "bidirectional"))
    )
    (net (code "161") (name "unconnected-(U$25-RB-PadP$3)") (class "Default")
      (node (ref "U$25") (pin "P$3") (pinfunction "RB_P$3") (pintype "bidirectional"))
    )
    (net (code "162") (name "unconnected-(U$26-LB-PadP$1)") (class "Default")
      (node (ref "U$26") (pin "P$1") (pinfunction "LB_P$1") (pintype "bidirectional"))
    )
    (net (code "163") (name "unconnected-(U$26-RT-PadP$4)") (class "Default")
      (node (ref "U$26") (pin "P$4") (pinfunction "RT_P$4") (pintype "bidirectional"))
    )
    (net (code "164") (name "unconnected-(U$28-RB-PadP$3)") (class "Default")
      (node (ref "U$28") (pin "P$3") (pinfunction "RB_P$3") (pintype "bidirectional"))
    )
    (net (code "165") (name "unconnected-(U$28-RT-PadP$4)") (class "Default")
      (node (ref "U$28") (pin "P$4") (pinfunction "RT_P$4") (pintype "bidirectional"))
    )
    (net (code "166") (name "unconnected-(U$29-LB-PadP$1)") (class "Default")
      (node (ref "U$29") (pin "P$1") (pinfunction "LB_P$1") (pintype "bidirectional"))
    )
    (net (code "167") (name "unconnected-(U$29-LT-PadP$2)") (class "Default")
      (node (ref "U$29") (pin "P$2") (pinfunction "LT_P$2") (pintype "bidirectional"))
    )
    (net (code "168") (name "unconnected-(U$29-RT-PadP$4)") (class "Default")
      (node (ref "U$29") (pin "P$4") (pinfunction "RT_P$4") (pintype "bidirectional"))
    )
    (net (code "169") (name "unconnected-(U$30-LB-PadP$1)") (class "Default")
      (node (ref "U$30") (pin "P$1") (pinfunction "LB_P$1") (pintype "bidirectional"))
    )
    (net (code "170") (name "unconnected-(U$30-LT-PadP$2)") (class "Default")
      (node (ref "U$30") (pin "P$2") (pinfunction "LT_P$2") (pintype "bidirectional"))
    )
    (net (code "171") (name "unconnected-(U$30-RB-PadP$3)") (class "Default")
      (node (ref "U$30") (pin "P$3") (pinfunction "RB_P$3") (pintype "bidirectional"))
    )
    (net (code "172") (name "unconnected-(U$30-RT-PadP$4)") (class "Default")
      (node (ref "U$30") (pin "P$4") (pinfunction "RT_P$4") (pintype "bidirectional"))
    )
    (net (code "173") (name "unconnected-(U$33-LB-PadP$1)") (class "Default")
      (node (ref "U$33") (pin "P$1") (pinfunction "LB_P$1") (pintype "bidirectional"))
    )
    (net (code "174") (name "unconnected-(U$34-RB-PadP$3)") (class "Default")
      (node (ref "U$34") (pin "P$3") (pinfunction "RB_P$3") (pintype "bidirectional"))
    )
    (net (code "175") (name "unconnected-(U$34-RT-PadP$4)") (class "Default")
      (node (ref "U$34") (pin "P$4") (pinfunction "RT_P$4") (pintype "bidirectional"))
    )
    (net (code "176") (name "unconnected-(U$35-RB-PadP$3)") (class "Default")
      (node (ref "U$35") (pin "P$3") (pinfunction "RB_P$3") (pintype "bidirectional"))
    )
    (net (code "177") (name "unconnected-(VFD-PadP$1)") (class "Default")
      (node (ref "VFD") (pin "P$1") (pinfunction "P$1_P$1") (pintype "bidirectional"))
    )
    (net (code "178") (name "unconnected-(VFD-PadP$2)") (class "Default")
      (node (ref "VFD") (pin "P$2") (pinfunction "P$2_P$2") (pintype "bidirectional"))
    )
    (net (code "179") (name "unconnected-(VFD-PadP$3)") (class "Default")
      (node (ref "VFD") (pin "P$3") (pinfunction "P$3_P$3") (pintype "bidirectional"))
    )
    (net (code "180") (name "unconnected-(VFD-PadP$4)") (class "Default")
      (node (ref "VFD") (pin "P$4") (pinfunction "P$4_P$4") (pintype "bidirectional"))
    )
    (net (code "181") (name "unconnected-(VFD-PadP$5)") (class "Default")
      (node (ref "VFD") (pin "P$5") (pinfunction "P$5_P$5") (pintype "bidirectional"))
    )
    (net (code "182") (name "unconnected-(VFD-PadP$6)") (class "Default")
      (node (ref "VFD") (pin "P$6") (pinfunction "P$6_P$6") (pintype "bidirectional"))
    )
    (net (code "183") (name "unconnected-(VFD-PadP$7)") (class "Default")
      (node (ref "VFD") (pin "P$7") (pinfunction "P$7_P$7") (pintype "bidirectional"))
    )
    (net (code "184") (name "unconnected-(VFD-PadP$8)") (class "Default")
      (node (ref "VFD") (pin "P$8") (pinfunction "P$8_P$8") (pintype "bidirectional"))
    )
    (net (code "185") (name "unconnected-(VFD-PadP$9)") (class "Default")
      (node (ref "VFD") (pin "P$9") (pinfunction "P$9_P$9") (pintype "bidirectional"))
    )
    (net (code "186") (name "unconnected-(VFD-PadP$10)") (class "Default")
      (node (ref "VFD") (pin "P$10") (pinfunction "P$10_P$10") (pintype "bidirectional"))
    )
    (net (code "187") (name "unconnected-(VFD-PadP$11)") (class "Default")
      (node (ref "VFD") (pin "P$11") (pinfunction "P$11_P$11") (pintype "bidirectional"))
    )
    (net (code "188") (name "unconnected-(VFD-PadP$12)") (class "Default")
      (node (ref "VFD") (pin "P$12") (pinfunction "P$12_P$12") (pintype "bidirectional"))
    )
    (net (code "189") (name "unconnected-(VFD-PadP$13)") (class "Default")
      (node (ref "VFD") (pin "P$13") (pinfunction "P$13_P$13") (pintype "bidirectional"))
    )
    (net (code "190") (name "unconnected-(VFD-PadP$14)") (class "Default")
      (node (ref "VFD") (pin "P$14") (pinfunction "P$14_P$14") (pintype "bidirectional"))
    )
    (net (code "191") (name "unconnected-(VFD-PadP$15)") (class "Default")
      (node (ref "VFD") (pin "P$15") (pinfunction "P$15_P$15") (pintype "bidirectional"))
    )
    (net (code "192") (name "unconnected-(VFD-PadP$16)") (class "Default")
      (node (ref "VFD") (pin "P$16") (pinfunction "P$16_P$16") (pintype "bidirectional"))
    )
    (net (code "193") (name "unconnected-(VFD-PadP$17)") (class "Default")
      (node (ref "VFD") (pin "P$17") (pinfunction "P$17_P$17") (pintype "bidirectional"))
    )
    (net (code "194") (name "unconnected-(VFD-PadP$18)") (class "Default")
      (node (ref "VFD") (pin "P$18") (pinfunction "P$18_P$18") (pintype "bidirectional"))
    )
    (net (code "195") (name "unconnected-(VFD-PadP$19)") (class "Default")
      (node (ref "VFD") (pin "P$19") (pinfunction "P$19_P$19") (pintype "bidirectional"))
    )
    (net (code "196") (name "unconnected-(VFD-PadP$20)") (class "Default")
      (node (ref "VFD") (pin "P$20") (pinfunction "P$20_P$20") (pintype "bidirectional"))
    )
    (net (code "197") (name "unconnected-(VFD-PadP$21)") (class "Default")
      (node (ref "VFD") (pin "P$21") (pinfunction "P$21_P$21") (pintype "bidirectional"))
    )
    (net (code "198") (name "unconnected-(VFD-PadP$22)") (class "Default")
      (node (ref "VFD") (pin "P$22") (pinfunction "P$22_P$22") (pintype "bidirectional"))
    )
    (net (code "199") (name "unconnected-(VFD-PadP$26)") (class "Default")
      (node (ref "VFD") (pin "P$26") (pinfunction "P$26_P$26") (pintype "bidirectional"))
    )
    (net (code "200") (name "unconnected-(VFD-PadP$27)") (class "Default")
      (node (ref "VFD") (pin "P$27") (pinfunction "P$27_P$27") (pintype "bidirectional"))
    )
    (net (code "201") (name "unconnected-(VFD-PadP$33)") (class "Default")
      (node (ref "VFD") (pin "P$33") (pinfunction "P$33_P$33") (pintype "bidirectional"))
    )
  )
)
